# Modular_RFPA_v103_DFM_03_26_22.net
KiCad netlist of a schematic drawn in EAGLE
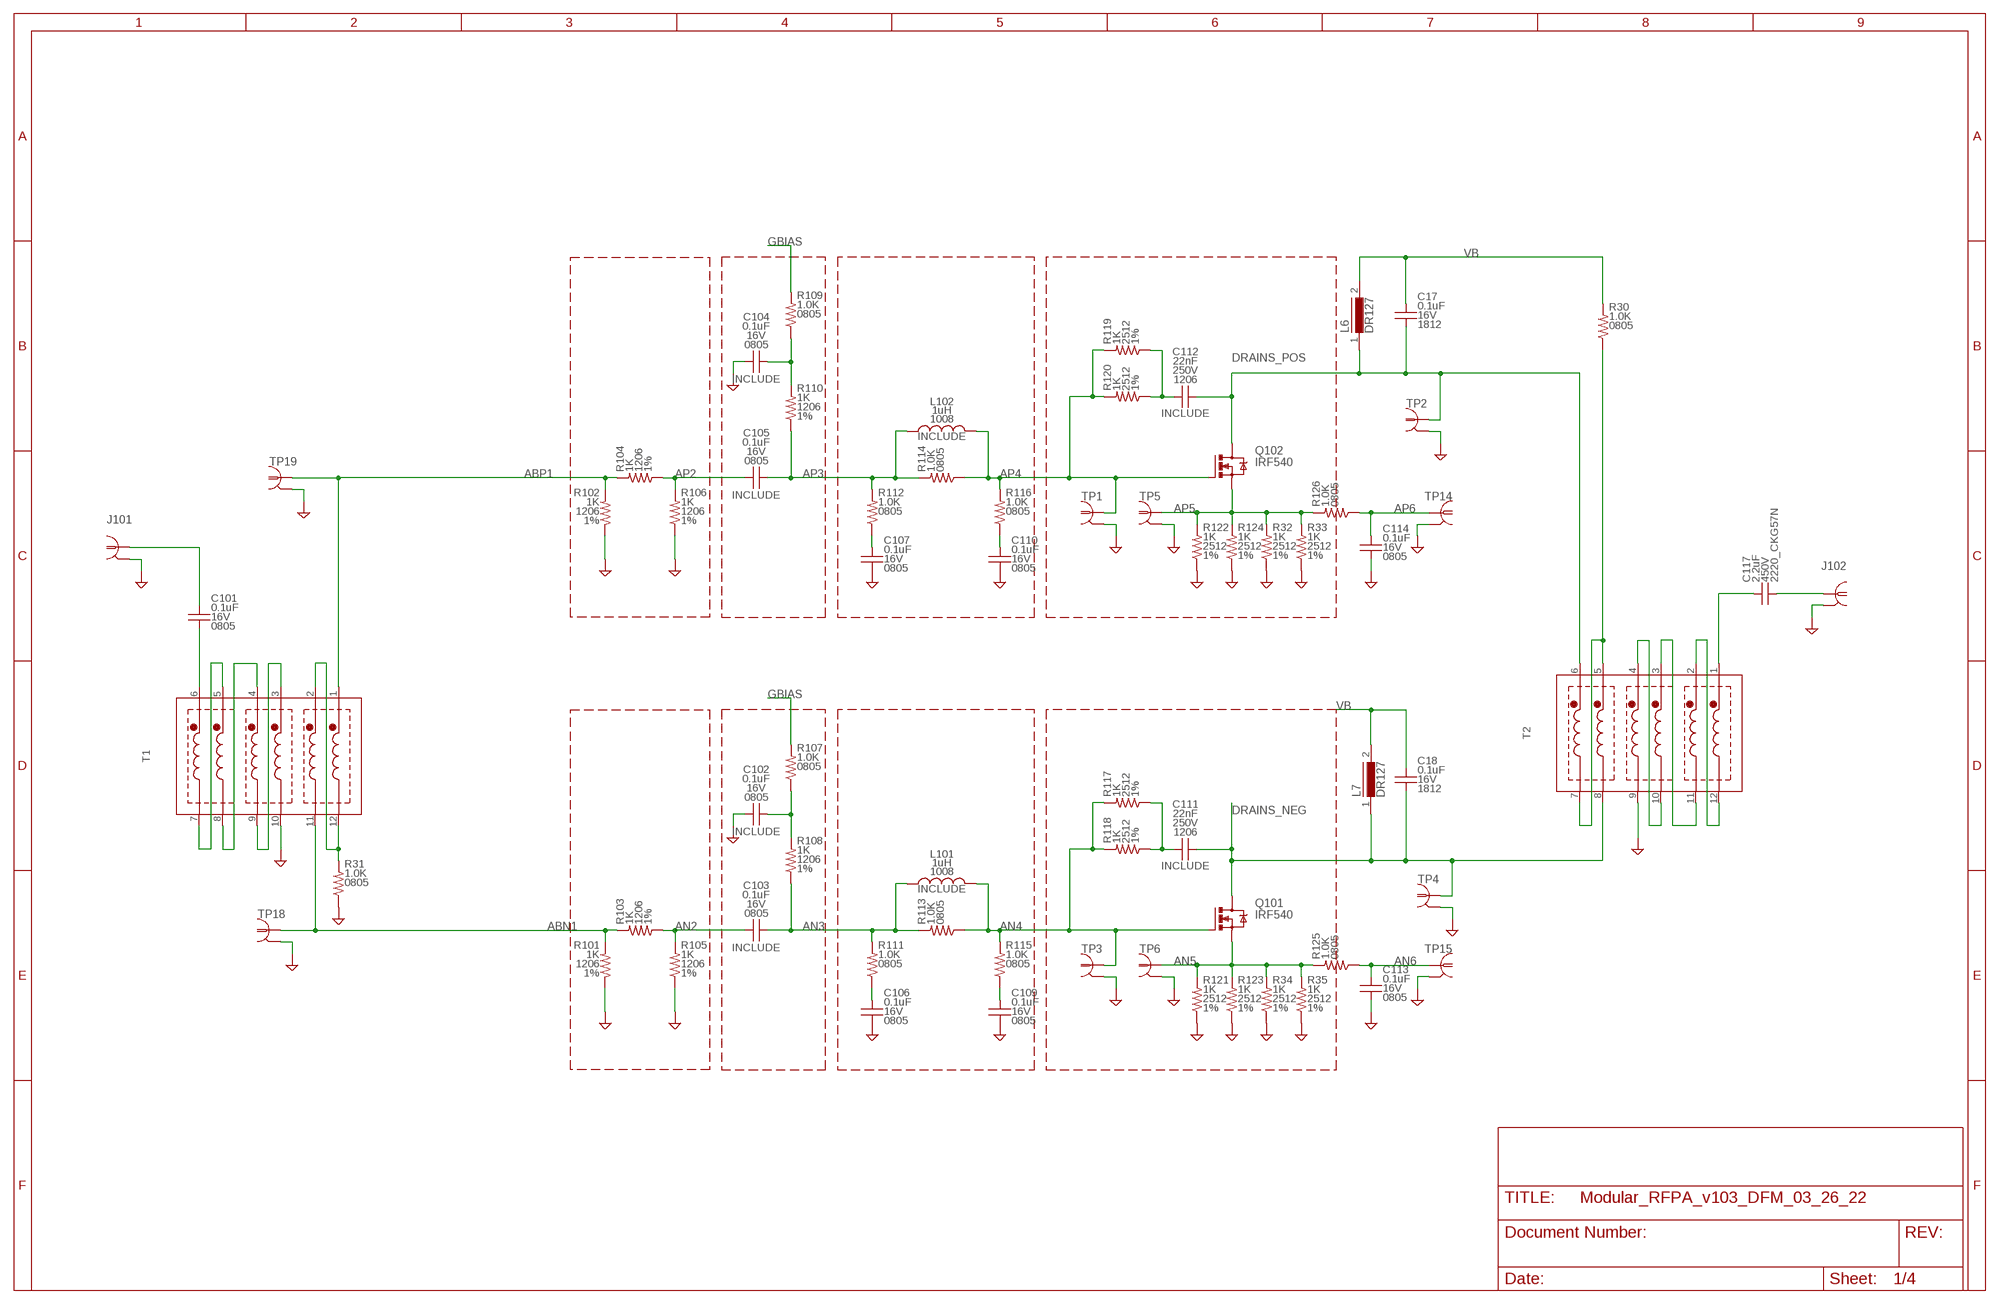
[diagram p0: schematic, sheet 1]
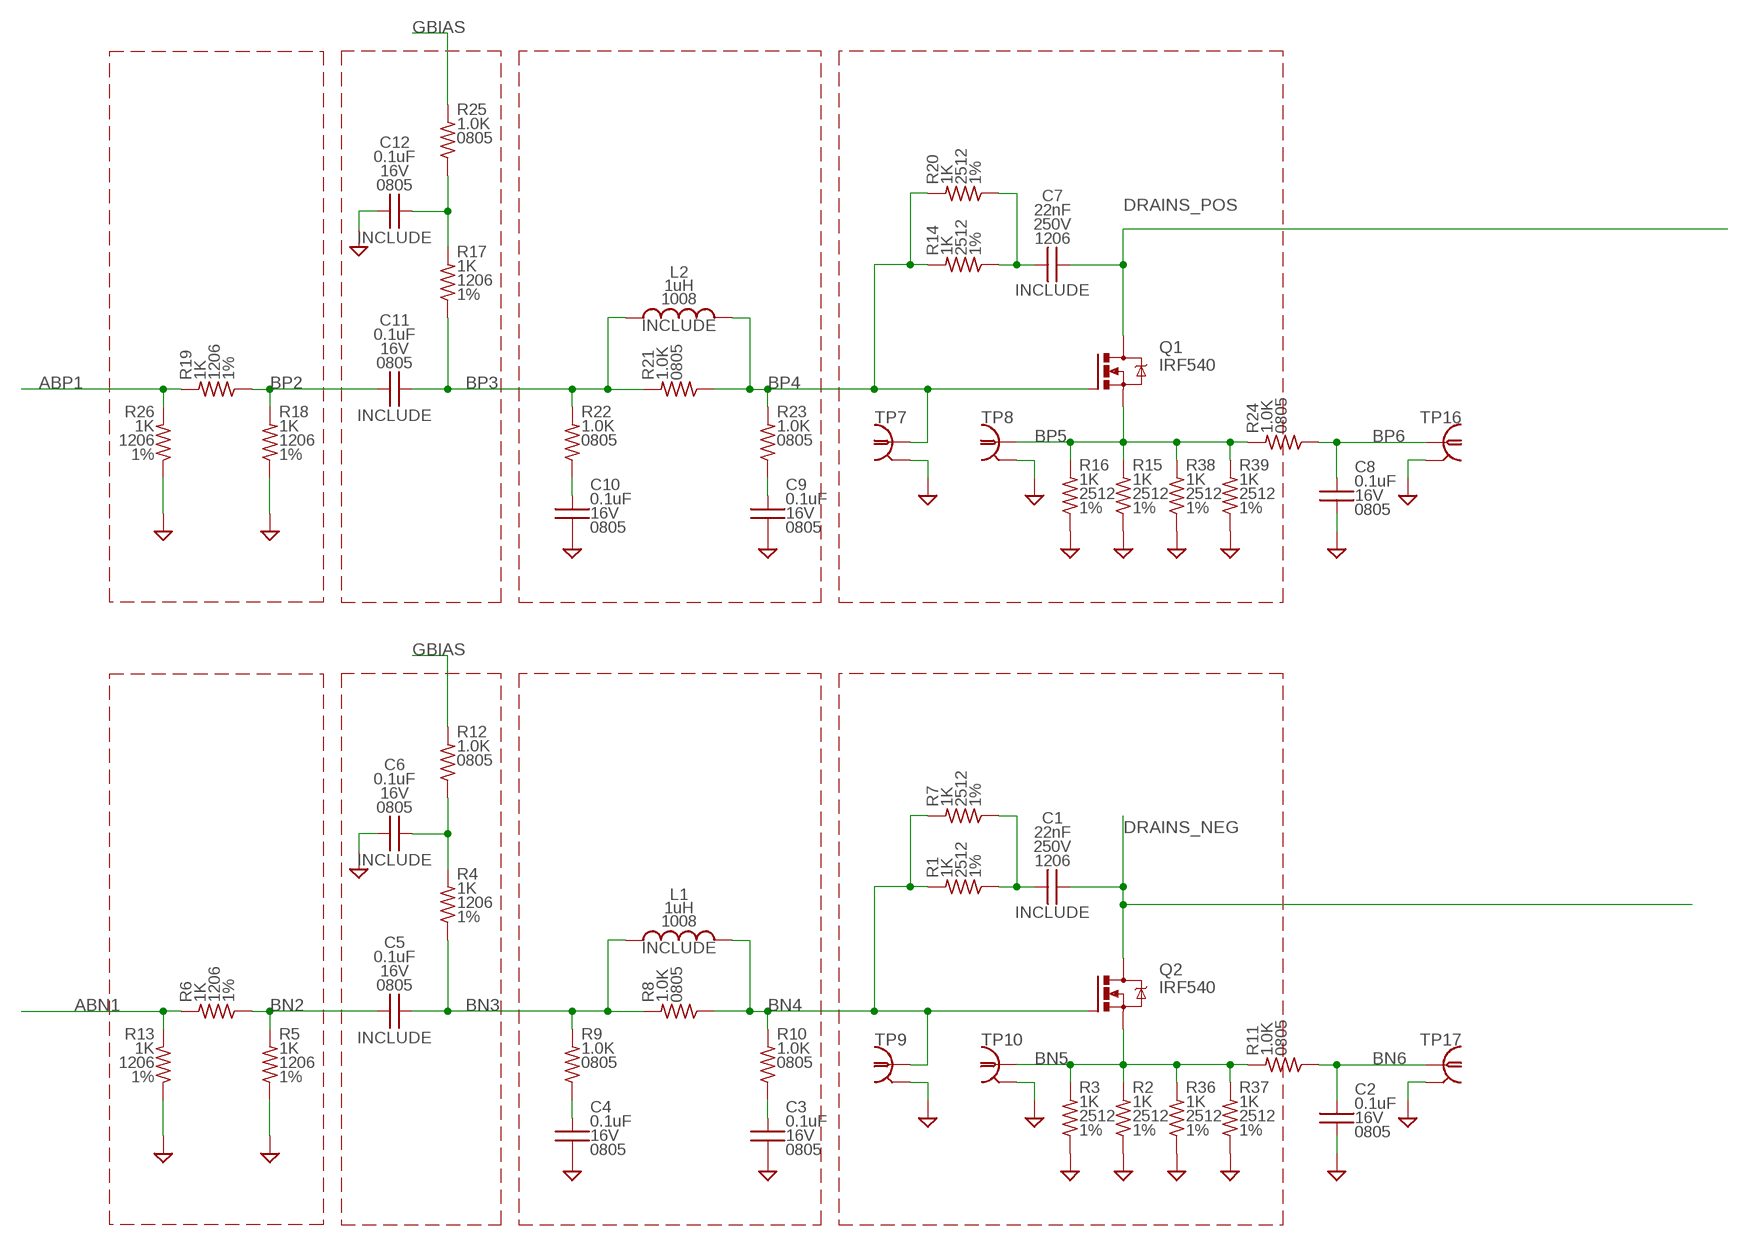
[diagram p1: schematic, sheet 2]
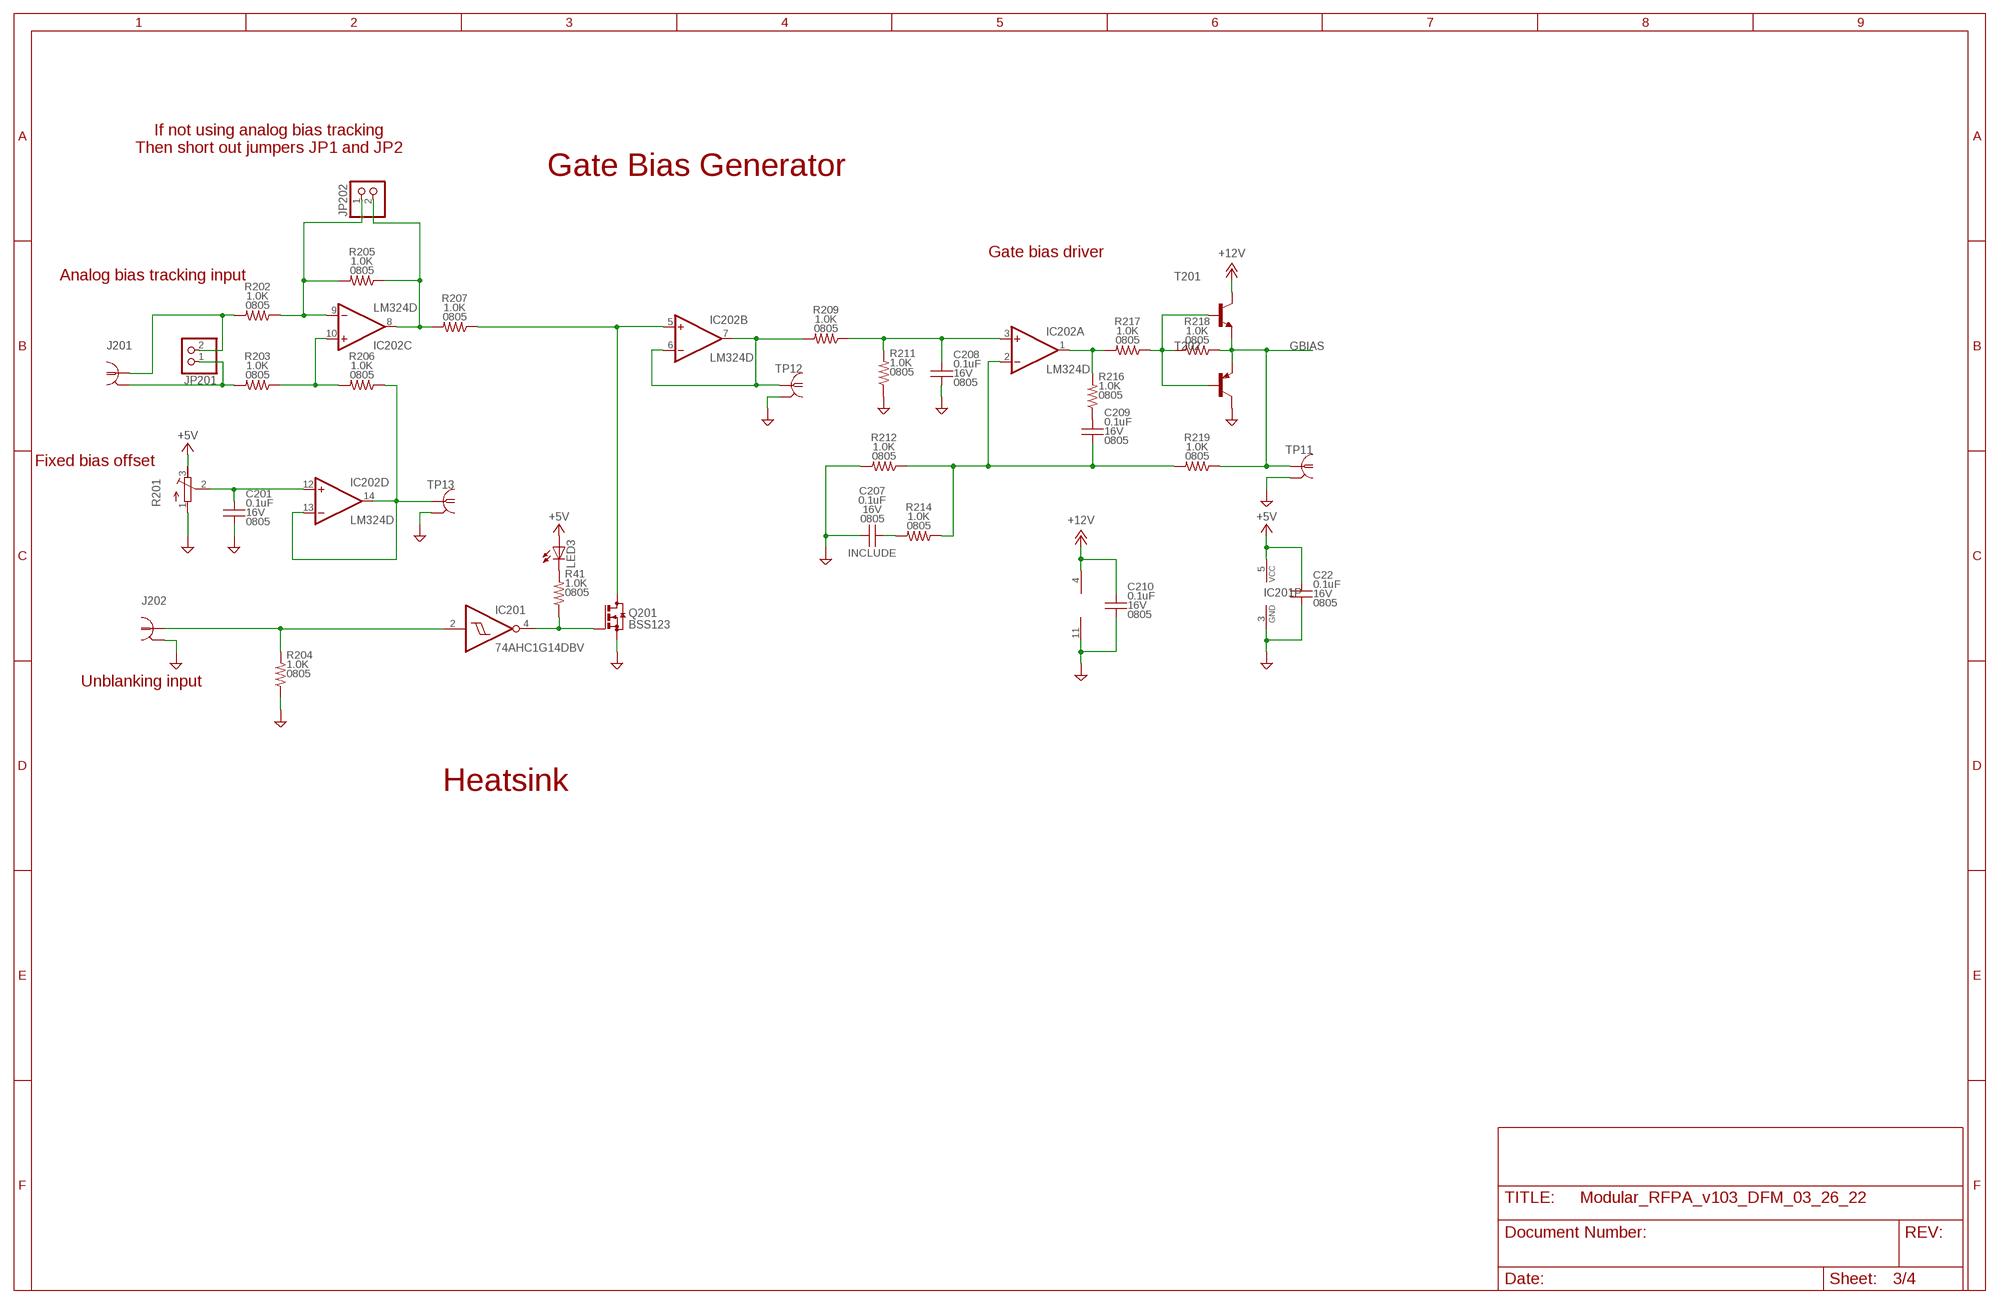
[diagram p2: schematic, sheet 3]
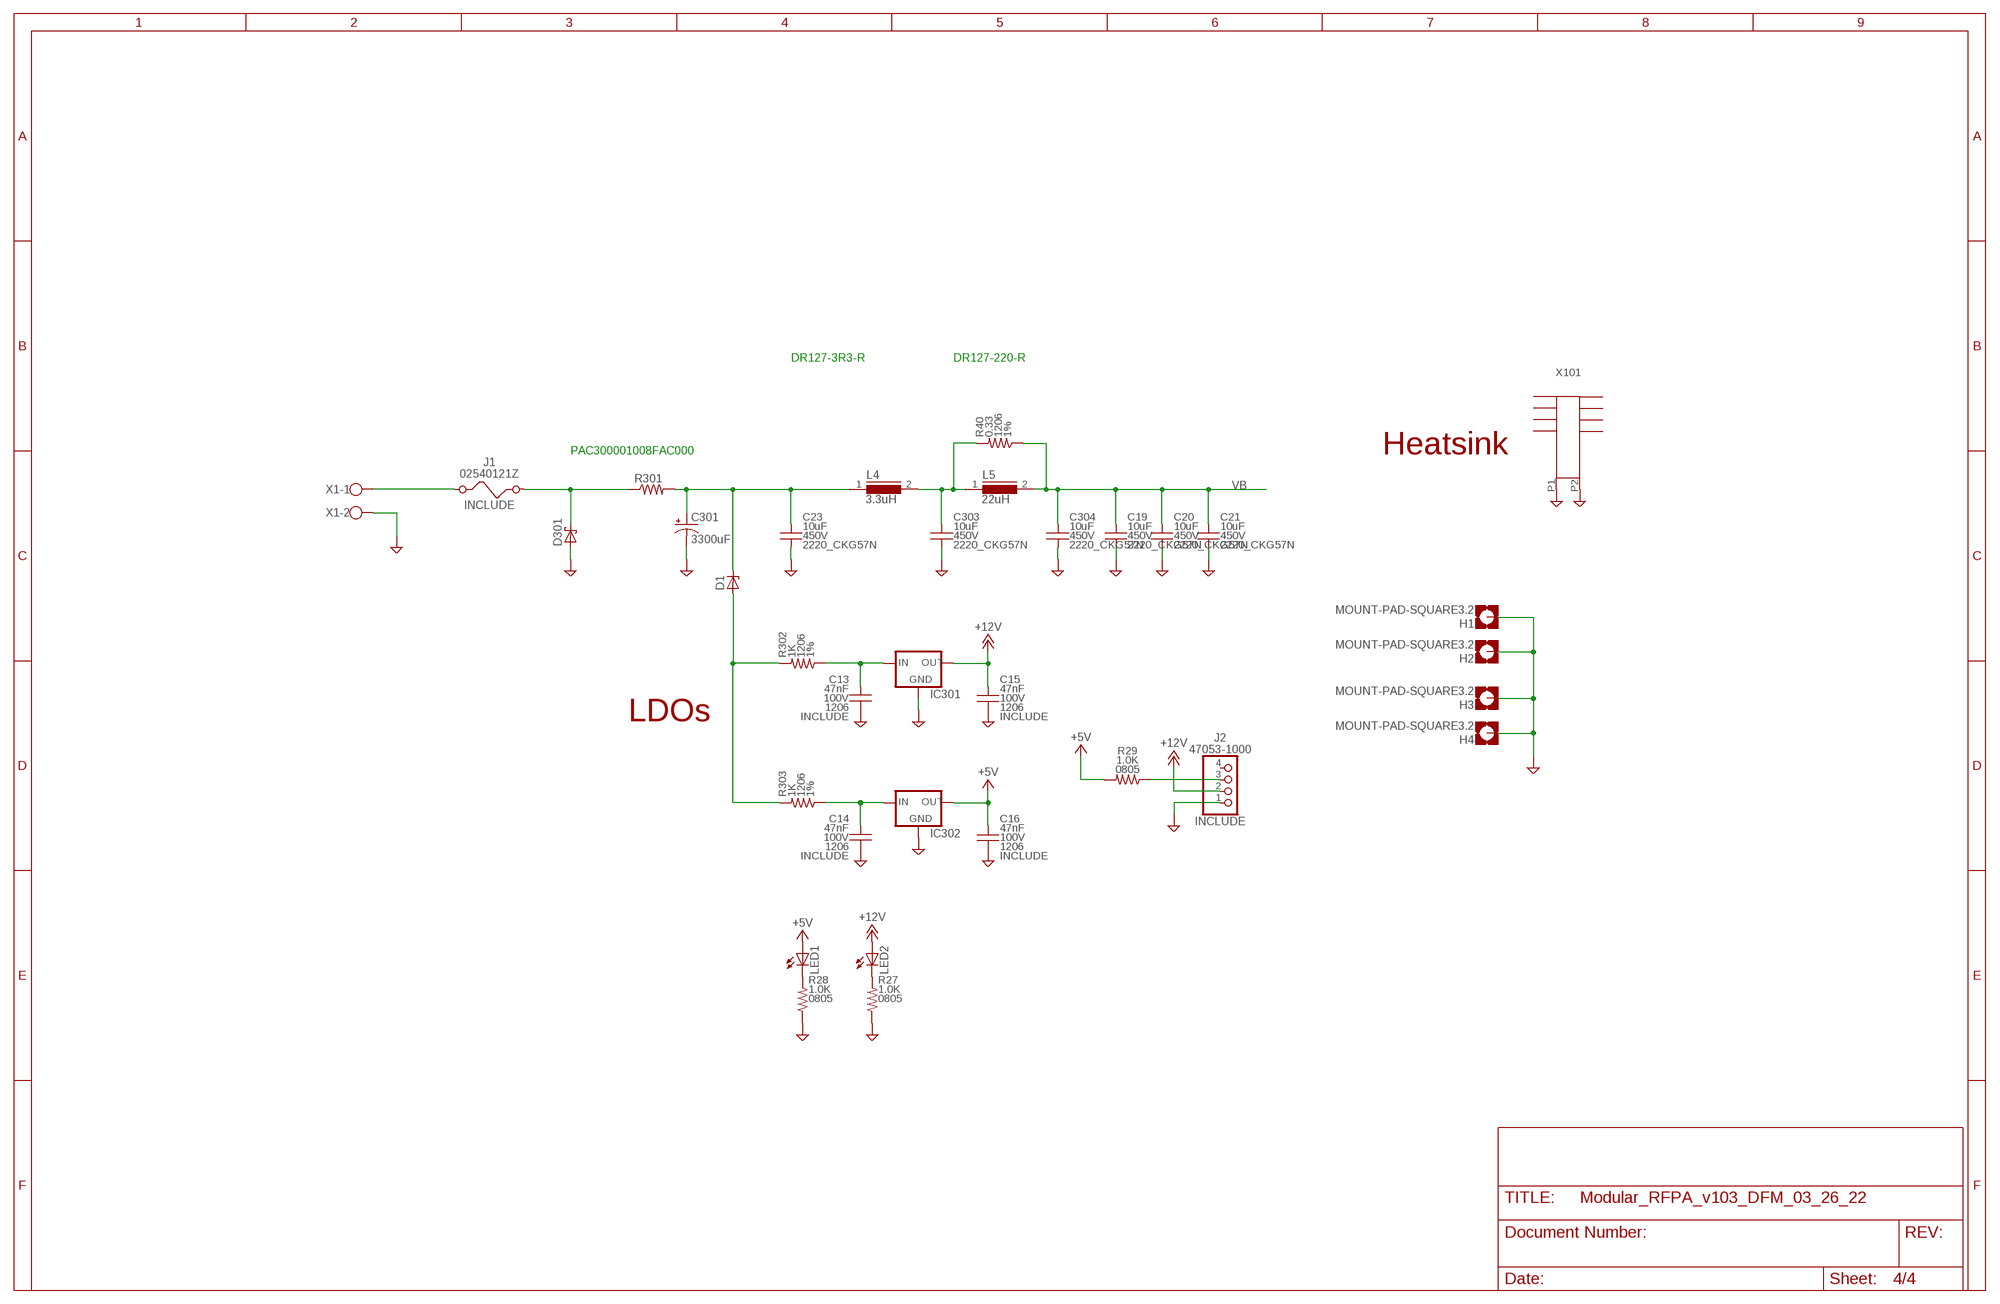
[diagram p3: schematic, sheet 4]

(export (version "E")
  (design (tool "Eeschema 10.0.6"))
  (components
    (comp (ref "C13")
      (value "47nF")
      (footprint "eagle-import:C1206")
      (fields (field (name "PARTNO") "C3216C0G2A473J115AC") (field (name "VOLTAGE") "100V"))
      (libsource (lib "eagle-import") (part "CC1206C-47N-100V-5%-1206-NP0"))
    )
    (comp (ref "C14")
      (value "47nF")
      (footprint "eagle-import:C1206")
      (fields (field (name "PARTNO") "C3216C0G2A473J115AC") (field (name "VOLTAGE") "100V"))
      (libsource (lib "eagle-import") (part "CC1206C-47N-100V-5%-1206-NP0"))
    )
    (comp (ref "C15")
      (value "47nF")
      (footprint "eagle-import:C1206")
      (fields (field (name "PARTNO") "C3216C0G2A473J115AC") (field (name "VOLTAGE") "100V"))
      (libsource (lib "eagle-import") (part "CC1206C-47N-100V-5%-1206-NP0"))
    )
    (comp (ref "C16")
      (value "47nF")
      (footprint "eagle-import:C1206")
      (fields (field (name "PARTNO") "C3216C0G2A473J115AC") (field (name "VOLTAGE") "100V"))
      (libsource (lib "eagle-import") (part "CC1206C-47N-100V-5%-1206-NP0"))
    )
    (comp (ref "C19")
      (value "10uF")
      (footprint "eagle-import:C2220_CKG57N")
      (fields (field (name "PARTNO") "CKG57NX7T2W225M500JJ") (field (name "VOLTAGE") "450V"))
      (libsource (lib "eagle-import") (part "CC2220_CKG57NC-2.2U-450V-20%-2220-X7T"))
    )
    (comp (ref "C20")
      (value "10uF")
      (footprint "eagle-import:C2220_CKG57N")
      (fields (field (name "PARTNO") "CKG57NX7T2W225M500JJ") (field (name "VOLTAGE") "450V"))
      (libsource (lib "eagle-import") (part "CC2220_CKG57NC-2.2U-450V-20%-2220-X7T"))
    )
    (comp (ref "C21")
      (value "10uF")
      (footprint "eagle-import:C2220_CKG57N")
      (fields (field (name "PARTNO") "CKG57NX7T2W225M500JJ") (field (name "VOLTAGE") "450V"))
      (libsource (lib "eagle-import") (part "CC2220_CKG57NC-2.2U-450V-20%-2220-X7T"))
    )
    (comp (ref "C23")
      (value "10uF")
      (footprint "eagle-import:C2220_CKG57N")
      (fields (field (name "PARTNO") "CKG57NX7T2W225M500JJ") (field (name "VOLTAGE") "450V"))
      (libsource (lib "eagle-import") (part "CC2220_CKG57NC-2.2U-450V-20%-2220-X7T"))
    )
    (comp (ref "C301")
      (value "3300uF")
      (footprint "eagle-import:EB25D")
      (libsource (lib "eagle-import") (part "CPOL-USE10-25"))
    )
    (comp (ref "C303")
      (value "10uF")
      (footprint "eagle-import:C2220_CKG57N")
      (fields (field (name "PARTNO") "CKG57NX7T2W225M500JJ") (field (name "VOLTAGE") "450V"))
      (libsource (lib "eagle-import") (part "CC2220_CKG57NC-2.2U-450V-20%-2220-X7T"))
    )
    (comp (ref "C304")
      (value "10uF")
      (footprint "eagle-import:C2220_CKG57N")
      (fields (field (name "PARTNO") "CKG57NX7T2W225M500JJ") (field (name "VOLTAGE") "450V"))
      (libsource (lib "eagle-import") (part "CC2220_CKG57NC-2.2U-450V-20%-2220-X7T"))
    )
    (comp (ref "D1")
      (value "ZENER-DIODEDO41Z10")
      (footprint "eagle-import:DO41Z10")
      (libsource (lib "eagle-import") (part "ZENER-DIODEDO41Z10"))
    )
    (comp (ref "D301")
      (value "SCHOTTKY-DIODESMC")
      (footprint "eagle-import:SMC")
      (libsource (lib "eagle-import") (part "SCHOTTKY-DIODESMC"))
    )
    (comp (ref "H1")
      (value "MOUNT-PAD-SQUARE3.2")
      (footprint "eagle-import:3,2-PAD-SQUARE")
      (libsource (lib "eagle-import") (part "MOUNT-PAD-SQUARE3.2"))
    )
    (comp (ref "H2")
      (value "MOUNT-PAD-SQUARE3.2")
      (footprint "eagle-import:3,2-PAD-SQUARE")
      (libsource (lib "eagle-import") (part "MOUNT-PAD-SQUARE3.2"))
    )
    (comp (ref "H3")
      (value "MOUNT-PAD-SQUARE3.2")
      (footprint "eagle-import:3,2-PAD-SQUARE")
      (libsource (lib "eagle-import") (part "MOUNT-PAD-SQUARE3.2"))
    )
    (comp (ref "H4")
      (value "MOUNT-PAD-SQUARE3.2")
      (footprint "eagle-import:3,2-PAD-SQUARE")
      (libsource (lib "eagle-import") (part "MOUNT-PAD-SQUARE3.2"))
    )
    (comp (ref "IC301")
      (value "78XXS")
      (footprint "eagle-import:78XXS")
      (libsource (lib "eagle-import") (part "78XXS"))
    )
    (comp (ref "IC302")
      (value "78XXS")
      (footprint "eagle-import:78XXS")
      (libsource (lib "eagle-import") (part "78XXS"))
    )
    (comp (ref "J1")
      (value "FUSE_2P")
      (footprint "eagle-import:02540121Z")
      (fields (field (name "PARTNO") "02540121Z"))
      (libsource (lib "eagle-import") (part "FUSE_2P"))
    )
    (comp (ref "J2")
      (value "KK_PCFAN")
      (footprint "eagle-import:47053-1000")
      (fields (field (name "PARTNO") "47053-1000"))
      (libsource (lib "eagle-import") (part "KK_PCFAN"))
    )
    (comp (ref "L4")
      (value "3.3uH")
      (footprint "eagle-import:DR127")
      (libsource (lib "eagle-import") (part "DR127"))
    )
    (comp (ref "L5")
      (value "22uH")
      (footprint "eagle-import:DR127")
      (libsource (lib "eagle-import") (part "DR127"))
    )
    (comp (ref "LED1")
      (value "LED5MM")
      (footprint "eagle-import:LED5MM")
      (libsource (lib "eagle-import") (part "LED5MM"))
    )
    (comp (ref "LED2")
      (value "LED5MM")
      (footprint "eagle-import:LED5MM")
      (libsource (lib "eagle-import") (part "LED5MM"))
    )
    (comp (ref "R27")
      (value "1.0K")
      (footprint "eagle-import:0805_IPC-7351B")
      (libsource (lib "eagle-import") (part "R0805_IPCR-1.0K-0.1%-0805-0.1W"))
    )
    (comp (ref "R28")
      (value "1.0K")
      (footprint "eagle-import:0805_IPC-7351B")
      (libsource (lib "eagle-import") (part "R0805_IPCR-1.0K-0.1%-0805-0.1W"))
    )
    (comp (ref "R29")
      (value "1.0K")
      (footprint "eagle-import:0805_IPC-7351B")
      (fields (field (name "PACKAGE") "0805"))
      (libsource (lib "eagle-import") (part "R0805_IPCR-1.0K-0.1%-0805-0.1W"))
    )
    (comp (ref "R40")
      (value "0.33")
      (footprint "eagle-import:R1206")
      (fields (field (name "POWER") "0.25"))
      (libsource (lib "eagle-import") (part "RR1206R-1.0K-1%-1206-0.25W"))
    )
    (comp (ref "R301")
      (value "R-US_0817/7V")
      (footprint "eagle-import:P0817V")
      (libsource (lib "eagle-import") (part "R-US_0817/7V"))
    )
    (comp (ref "R302")
      (value "1K")
      (footprint "eagle-import:R1206")
      (fields (field (name "POWER") "0.25"))
      (libsource (lib "eagle-import") (part "RR1206R-1.0K-1%-1206-0.25W"))
    )
    (comp (ref "R303")
      (value "1K")
      (footprint "eagle-import:R1206")
      (fields (field (name "POWER") "0.25"))
      (libsource (lib "eagle-import") (part "RR1206R-1.0K-1%-1206-0.25W"))
    )
    (comp (ref "X1")
      (value "W237-102")
      (footprint "eagle-import:W237-102")
      (fields (field (name "MPN") "237-102"))
      (libsource (lib "eagle-import") (part "W237-102"))
    )
    (comp (ref "X101")
      (value "HEATSINK_OMNI_DUAL30-75-D")
      (footprint "eagle-import:OMNI-UNI-30-75-D")
      (libsource (lib "eagle-import") (part "HEATSINK_OMNI_DUAL30-75-D"))
    )
    (comp (ref "C1")
      (value "22nF")
      (footprint "eagle-import:C1206")
      (fields
        (field (name "BOM") "INCLUDE")
        (field (name "PACKAGE") "1206")
        (field (name "PARTNO") "C3216NP02E223J160AA")
        (field (name "VOLTAGE") "250V")
      )
      (libsource (lib "eagle-import") (part "CC1206C-22N-250V-5%-1206-NP0"))
    )
    (comp (ref "C2")
      (value "0.1uF")
      (footprint "eagle-import:0805_IPC-7351B")
      (fields (field (name "VOLTAGE") "16V"))
      (libsource (lib "eagle-import") (part "C0805_IPCC-0.1U-16V-0805-X7R"))
    )
    (comp (ref "C3")
      (value "0.1uF")
      (footprint "eagle-import:0805_IPC-7351B")
      (fields (field (name "VOLTAGE") "16V"))
      (libsource (lib "eagle-import") (part "C0805_IPCC-0.1U-16V-0805-X7R"))
    )
    (comp (ref "C4")
      (value "0.1uF")
      (footprint "eagle-import:0805_IPC-7351B")
      (fields (field (name "VOLTAGE") "16V"))
      (libsource (lib "eagle-import") (part "C0805_IPCC-0.1U-16V-0805-X7R"))
    )
    (comp (ref "C5")
      (value "0.1uF")
      (footprint "eagle-import:0805_IPC-7351B")
      (fields (field (name "PACKAGE") "0805") (field (name "VOLTAGE") "16V") (field (name "BOM") "INCLUDE"))
      (libsource (lib "eagle-import") (part "C0805_IPCC-0.1U-16V-0805-X7R"))
    )
    (comp (ref "C6")
      (value "0.1uF")
      (footprint "eagle-import:0805_IPC-7351B")
      (fields (field (name "PACKAGE") "0805") (field (name "VOLTAGE") "16V") (field (name "BOM") "INCLUDE"))
      (libsource (lib "eagle-import") (part "C0805_IPCC-0.1U-16V-0805-X7R"))
    )
    (comp (ref "C7")
      (value "22nF")
      (footprint "eagle-import:C1206")
      (fields
        (field (name "BOM") "INCLUDE")
        (field (name "PACKAGE") "1206")
        (field (name "PARTNO") "C3216NP02E223J160AA")
        (field (name "VOLTAGE") "250V")
      )
      (libsource (lib "eagle-import") (part "CC1206C-22N-250V-5%-1206-NP0"))
    )
    (comp (ref "C8")
      (value "0.1uF")
      (footprint "eagle-import:0805_IPC-7351B")
      (fields (field (name "VOLTAGE") "16V"))
      (libsource (lib "eagle-import") (part "C0805_IPCC-0.1U-16V-0805-X7R"))
    )
    (comp (ref "C9")
      (value "0.1uF")
      (footprint "eagle-import:0805_IPC-7351B")
      (fields (field (name "VOLTAGE") "16V"))
      (libsource (lib "eagle-import") (part "C0805_IPCC-0.1U-16V-0805-X7R"))
    )
    (comp (ref "C10")
      (value "0.1uF")
      (footprint "eagle-import:0805_IPC-7351B")
      (fields (field (name "VOLTAGE") "16V"))
      (libsource (lib "eagle-import") (part "C0805_IPCC-0.1U-16V-0805-X7R"))
    )
    (comp (ref "C11")
      (value "0.1uF")
      (footprint "eagle-import:0805_IPC-7351B")
      (fields (field (name "PACKAGE") "0805") (field (name "VOLTAGE") "16V") (field (name "BOM") "INCLUDE"))
      (libsource (lib "eagle-import") (part "C0805_IPCC-0.1U-16V-0805-X7R"))
    )
    (comp (ref "C12")
      (value "0.1uF")
      (footprint "eagle-import:0805_IPC-7351B")
      (fields (field (name "PACKAGE") "0805") (field (name "VOLTAGE") "16V") (field (name "BOM") "INCLUDE"))
      (libsource (lib "eagle-import") (part "C0805_IPCC-0.1U-16V-0805-X7R"))
    )
    (comp (ref "L1")
      (value "1uH")
      (footprint "eagle-import:L1008")
      (fields (field (name "PARTNO") "1008CS-102XJEC"))
      (libsource (lib "eagle-import") (part "L_CHIP1008L-1.0U-AIR-5%-1008-0.37A"))
    )
    (comp (ref "L2")
      (value "1uH")
      (footprint "eagle-import:L1008")
      (fields (field (name "PARTNO") "1008CS-102XJEC"))
      (libsource (lib "eagle-import") (part "L_CHIP1008L-1.0U-AIR-5%-1008-0.37A"))
    )
    (comp (ref "Q1")
      (value "IRF540")
      (footprint "eagle-import:TO220BV")
      (libsource (lib "eagle-import") (part "IRF540"))
    )
    (comp (ref "Q2")
      (value "IRF540")
      (footprint "eagle-import:TO220BV")
      (libsource (lib "eagle-import") (part "IRF540"))
    )
    (comp (ref "R1")
      (value "1K")
      (footprint "eagle-import:R2512")
      (fields (field (name "POWER") "1"))
      (libsource (lib "eagle-import") (part "RR2512R-1K-1%-2512-1W"))
    )
    (comp (ref "R2")
      (value "1K")
      (footprint "eagle-import:R2512")
      (fields (field (name "POWER") "1"))
      (libsource (lib "eagle-import") (part "RR2512R-1K-1%-2512-1W"))
    )
    (comp (ref "R3")
      (value "1K")
      (footprint "eagle-import:R2512")
      (fields (field (name "POWER") "1"))
      (libsource (lib "eagle-import") (part "RR2512R-1K-1%-2512-1W"))
    )
    (comp (ref "R4")
      (value "1K")
      (footprint "eagle-import:R1206")
      (fields (field (name "POWER") "0.25"))
      (libsource (lib "eagle-import") (part "RR1206R-1.0K-1%-1206-0.25W"))
    )
    (comp (ref "R5")
      (value "1K")
      (footprint "eagle-import:R1206")
      (fields (field (name "POWER") "0.25"))
      (libsource (lib "eagle-import") (part "RR1206R-1.0K-1%-1206-0.25W"))
    )
    (comp (ref "R6")
      (value "1K")
      (footprint "eagle-import:R1206")
      (fields (field (name "POWER") "0.25"))
      (libsource (lib "eagle-import") (part "RR1206R-1.0K-1%-1206-0.25W"))
    )
    (comp (ref "R7")
      (value "1K")
      (footprint "eagle-import:R2512")
      (fields (field (name "POWER") "1"))
      (libsource (lib "eagle-import") (part "RR2512R-1K-1%-2512-1W"))
    )
    (comp (ref "R8")
      (value "1.0K")
      (footprint "eagle-import:0805_IPC-7351B")
      (libsource (lib "eagle-import") (part "R0805_IPCR-1.0K-0.1%-0805-0.1W"))
    )
    (comp (ref "R9")
      (value "1.0K")
      (footprint "eagle-import:0805_IPC-7351B")
      (libsource (lib "eagle-import") (part "R0805_IPCR-1.0K-0.1%-0805-0.1W"))
    )
    (comp (ref "R10")
      (value "1.0K")
      (footprint "eagle-import:0805_IPC-7351B")
      (libsource (lib "eagle-import") (part "R0805_IPCR-1.0K-0.1%-0805-0.1W"))
    )
    (comp (ref "R11")
      (value "1.0K")
      (footprint "eagle-import:0805_IPC-7351B")
      (libsource (lib "eagle-import") (part "R0805_IPCR-1.0K-0.1%-0805-0.1W"))
    )
    (comp (ref "R12")
      (value "1.0K")
      (footprint "eagle-import:0805_IPC-7351B")
      (libsource (lib "eagle-import") (part "R0805_IPCR-1.0K-0.1%-0805-0.1W"))
    )
    (comp (ref "R13")
      (value "1K")
      (footprint "eagle-import:R1206")
      (fields (field (name "POWER") "0.25"))
      (libsource (lib "eagle-import") (part "RR1206R-1.0K-1%-1206-0.25W"))
    )
    (comp (ref "R14")
      (value "1K")
      (footprint "eagle-import:R2512")
      (fields (field (name "POWER") "1"))
      (libsource (lib "eagle-import") (part "RR2512R-1K-1%-2512-1W"))
    )
    (comp (ref "R15")
      (value "1K")
      (footprint "eagle-import:R2512")
      (fields (field (name "POWER") "1"))
      (libsource (lib "eagle-import") (part "RR2512R-1K-1%-2512-1W"))
    )
    (comp (ref "R16")
      (value "1K")
      (footprint "eagle-import:R2512")
      (fields (field (name "POWER") "1"))
      (libsource (lib "eagle-import") (part "RR2512R-1K-1%-2512-1W"))
    )
    (comp (ref "R17")
      (value "1K")
      (footprint "eagle-import:R1206")
      (fields (field (name "POWER") "0.25"))
      (libsource (lib "eagle-import") (part "RR1206R-1.0K-1%-1206-0.25W"))
    )
    (comp (ref "R18")
      (value "1K")
      (footprint "eagle-import:R1206")
      (fields (field (name "POWER") "0.25"))
      (libsource (lib "eagle-import") (part "RR1206R-1.0K-1%-1206-0.25W"))
    )
    (comp (ref "R19")
      (value "1K")
      (footprint "eagle-import:R1206")
      (fields (field (name "POWER") "0.25"))
      (libsource (lib "eagle-import") (part "RR1206R-1.0K-1%-1206-0.25W"))
    )
    (comp (ref "R20")
      (value "1K")
      (footprint "eagle-import:R2512")
      (fields (field (name "POWER") "1"))
      (libsource (lib "eagle-import") (part "RR2512R-1K-1%-2512-1W"))
    )
    (comp (ref "R21")
      (value "1.0K")
      (footprint "eagle-import:0805_IPC-7351B")
      (libsource (lib "eagle-import") (part "R0805_IPCR-1.0K-0.1%-0805-0.1W"))
    )
    (comp (ref "R22")
      (value "1.0K")
      (footprint "eagle-import:0805_IPC-7351B")
      (libsource (lib "eagle-import") (part "R0805_IPCR-1.0K-0.1%-0805-0.1W"))
    )
    (comp (ref "R23")
      (value "1.0K")
      (footprint "eagle-import:0805_IPC-7351B")
      (libsource (lib "eagle-import") (part "R0805_IPCR-1.0K-0.1%-0805-0.1W"))
    )
    (comp (ref "R24")
      (value "1.0K")
      (footprint "eagle-import:0805_IPC-7351B")
      (libsource (lib "eagle-import") (part "R0805_IPCR-1.0K-0.1%-0805-0.1W"))
    )
    (comp (ref "R25")
      (value "1.0K")
      (footprint "eagle-import:0805_IPC-7351B")
      (libsource (lib "eagle-import") (part "R0805_IPCR-1.0K-0.1%-0805-0.1W"))
    )
    (comp (ref "R26")
      (value "1K")
      (footprint "eagle-import:R1206")
      (fields (field (name "POWER") "0.25"))
      (libsource (lib "eagle-import") (part "RR1206R-1.0K-1%-1206-0.25W"))
    )
    (comp (ref "R36")
      (value "1K")
      (footprint "eagle-import:R2512")
      (fields (field (name "POWER") "1"))
      (libsource (lib "eagle-import") (part "RR2512R-1K-1%-2512-1W"))
    )
    (comp (ref "R37")
      (value "1K")
      (footprint "eagle-import:R2512")
      (fields (field (name "POWER") "1"))
      (libsource (lib "eagle-import") (part "RR2512R-1K-1%-2512-1W"))
    )
    (comp (ref "R38")
      (value "1K")
      (footprint "eagle-import:R2512")
      (fields (field (name "POWER") "1"))
      (libsource (lib "eagle-import") (part "RR2512R-1K-1%-2512-1W"))
    )
    (comp (ref "R39")
      (value "1K")
      (footprint "eagle-import:R2512")
      (fields (field (name "POWER") "1"))
      (libsource (lib "eagle-import") (part "RR2512R-1K-1%-2512-1W"))
    )
    (comp (ref "TP7")
      (value "PROBE_TPTP_5MM")
      (footprint "eagle-import:PROBE_TP_5MM")
      (libsource (lib "eagle-import") (part "PROBE_TPTP_5MM"))
    )
    (comp (ref "TP8")
      (value "PROBE_TPTP_7P5MM")
      (footprint "eagle-import:PROBE_TP_7P5MM")
      (libsource (lib "eagle-import") (part "PROBE_TPTP_7P5MM"))
    )
    (comp (ref "TP9")
      (value "PROBE_TPTP_5MM")
      (footprint "eagle-import:PROBE_TP_5MM")
      (libsource (lib "eagle-import") (part "PROBE_TPTP_5MM"))
    )
    (comp (ref "TP10")
      (value "PROBE_TPTP_5MM")
      (footprint "eagle-import:PROBE_TP_5MM")
      (libsource (lib "eagle-import") (part "PROBE_TPTP_5MM"))
    )
    (comp (ref "TP16")
      (value "PROBE_TPTP_5MM")
      (footprint "eagle-import:PROBE_TP_5MM")
      (libsource (lib "eagle-import") (part "PROBE_TPTP_5MM"))
    )
    (comp (ref "TP17")
      (value "PROBE_TPTP_7P5MM")
      (footprint "eagle-import:PROBE_TP_7P5MM")
      (libsource (lib "eagle-import") (part "PROBE_TPTP_7P5MM"))
    )
    (comp (ref "C22")
      (value "0.1uF")
      (footprint "eagle-import:0805_IPC-7351B")
      (fields (field (name "VOLTAGE") "16V"))
      (libsource (lib "eagle-import") (part "C0805_IPCC-0.1U-16V-0805-X7R"))
    )
    (comp (ref "C201")
      (value "0.1uF")
      (footprint "eagle-import:0805_IPC-7351B")
      (fields (field (name "VOLTAGE") "16V"))
      (libsource (lib "eagle-import") (part "C0805_IPCC-0.1U-16V-0805-X7R"))
    )
    (comp (ref "C207")
      (value "0.1uF")
      (footprint "eagle-import:0805_IPC-7351B")
      (fields (field (name "PACKAGE") "0805") (field (name "VOLTAGE") "16V") (field (name "BOM") "INCLUDE"))
      (libsource (lib "eagle-import") (part "C0805_IPCC-0.1U-16V-0805-X7R"))
    )
    (comp (ref "C208")
      (value "0.1uF")
      (footprint "eagle-import:0805_IPC-7351B")
      (fields (field (name "VOLTAGE") "16V"))
      (libsource (lib "eagle-import") (part "C0805_IPCC-0.1U-16V-0805-X7R"))
    )
    (comp (ref "C209")
      (value "0.1uF")
      (footprint "eagle-import:0805_IPC-7351B")
      (fields (field (name "VOLTAGE") "16V"))
      (libsource (lib "eagle-import") (part "C0805_IPCC-0.1U-16V-0805-X7R"))
    )
    (comp (ref "C210")
      (value "0.1uF")
      (footprint "eagle-import:0805_IPC-7351B")
      (fields (field (name "VOLTAGE") "16V"))
      (libsource (lib "eagle-import") (part "C0805_IPCC-0.1U-16V-0805-X7R"))
    )
    (comp (ref "IC201")
      (value "74AHC1G14DBV")
      (footprint "eagle-import:SOT23-5")
      (libsource (lib "eagle-import") (part "741G14DBVAHC"))
    )
    (comp (ref "IC202")
      (value "LM324D")
      (footprint "eagle-import:SO14")
      (libsource (lib "eagle-import") (part "LM324D"))
    )
    (comp (ref "J201")
      (value "COAXBNC_EDGE")
      (footprint "eagle-import:BNC_EDGE")
      (libsource (lib "eagle-import") (part "COAXBNC_EDGE"))
    )
    (comp (ref "J202")
      (value "COAXBNC_EDGE")
      (footprint "eagle-import:BNC_EDGE")
      (libsource (lib "eagle-import") (part "COAXBNC_EDGE"))
    )
    (comp (ref "JP201")
      (value "PINHD-1X2")
      (footprint "eagle-import:1X02")
      (libsource (lib "eagle-import") (part "PINHD-1X2"))
    )
    (comp (ref "JP202")
      (value "PINHD-1X2")
      (footprint "eagle-import:1X02")
      (libsource (lib "eagle-import") (part "PINHD-1X2"))
    )
    (comp (ref "LED3")
      (value "LED5MM")
      (footprint "eagle-import:LED5MM")
      (libsource (lib "eagle-import") (part "LED5MM"))
    )
    (comp (ref "Q201")
      (value "BSS123")
      (footprint "eagle-import:SOT23")
      (libsource (lib "eagle-import") (part "BSS123"))
    )
    (comp (ref "R41")
      (value "1.0K")
      (footprint "eagle-import:0805_IPC-7351B")
      (libsource (lib "eagle-import") (part "R0805_IPCR-1.0K-0.1%-0805-0.1W"))
    )
    (comp (ref "R201")
      (value "R-TRIMM3299W")
      (footprint "eagle-import:RTRIM3299W")
      (libsource (lib "eagle-import") (part "R-TRIMM3299W"))
    )
    (comp (ref "R202")
      (value "1.0K")
      (footprint "eagle-import:0805_IPC-7351B")
      (fields (field (name "PACKAGE") "0805"))
      (libsource (lib "eagle-import") (part "R0805_IPCR-1.0K-0.1%-0805-0.1W"))
    )
    (comp (ref "R203")
      (value "1.0K")
      (footprint "eagle-import:0805_IPC-7351B")
      (fields (field (name "PACKAGE") "0805"))
      (libsource (lib "eagle-import") (part "R0805_IPCR-1.0K-0.1%-0805-0.1W"))
    )
    (comp (ref "R204")
      (value "1.0K")
      (footprint "eagle-import:0805_IPC-7351B")
      (libsource (lib "eagle-import") (part "R0805_IPCR-1.0K-0.1%-0805-0.1W"))
    )
    (comp (ref "R205")
      (value "1.0K")
      (footprint "eagle-import:0805_IPC-7351B")
      (fields (field (name "PACKAGE") "0805"))
      (libsource (lib "eagle-import") (part "R0805_IPCR-1.0K-0.1%-0805-0.1W"))
    )
    (comp (ref "R206")
      (value "1.0K")
      (footprint "eagle-import:0805_IPC-7351B")
      (fields (field (name "PACKAGE") "0805"))
      (libsource (lib "eagle-import") (part "R0805_IPCR-1.0K-0.1%-0805-0.1W"))
    )
    (comp (ref "R207")
      (value "1.0K")
      (footprint "eagle-import:0805_IPC-7351B")
      (fields (field (name "PACKAGE") "0805"))
      (libsource (lib "eagle-import") (part "R0805_IPCR-1.0K-0.1%-0805-0.1W"))
    )
    (comp (ref "R209")
      (value "1.0K")
      (footprint "eagle-import:0805_IPC-7351B")
      (fields (field (name "PACKAGE") "0805"))
      (libsource (lib "eagle-import") (part "R0805_IPCR-1.0K-0.1%-0805-0.1W"))
    )
    (comp (ref "R211")
      (value "1.0K")
      (footprint "eagle-import:0805_IPC-7351B")
      (libsource (lib "eagle-import") (part "R0805_IPCR-1.0K-0.1%-0805-0.1W"))
    )
    (comp (ref "R212")
      (value "1.0K")
      (footprint "eagle-import:0805_IPC-7351B")
      (fields (field (name "PACKAGE") "0805"))
      (libsource (lib "eagle-import") (part "R0805_IPCR-1.0K-0.1%-0805-0.1W"))
    )
    (comp (ref "R214")
      (value "1.0K")
      (footprint "eagle-import:0805_IPC-7351B")
      (fields (field (name "PACKAGE") "0805"))
      (libsource (lib "eagle-import") (part "R0805_IPCR-1.0K-0.1%-0805-0.1W"))
    )
    (comp (ref "R216")
      (value "1.0K")
      (footprint "eagle-import:0805_IPC-7351B")
      (libsource (lib "eagle-import") (part "R0805_IPCR-1.0K-0.1%-0805-0.1W"))
    )
    (comp (ref "R217")
      (value "1.0K")
      (footprint "eagle-import:0805_IPC-7351B")
      (fields (field (name "PACKAGE") "0805"))
      (libsource (lib "eagle-import") (part "R0805_IPCR-1.0K-0.1%-0805-0.1W"))
    )
    (comp (ref "R218")
      (value "1.0K")
      (footprint "eagle-import:0805_IPC-7351B")
      (fields (field (name "PACKAGE") "0805"))
      (libsource (lib "eagle-import") (part "R0805_IPCR-1.0K-0.1%-0805-0.1W"))
    )
    (comp (ref "R219")
      (value "1.0K")
      (footprint "eagle-import:0805_IPC-7351B")
      (fields (field (name "PACKAGE") "0805"))
      (libsource (lib "eagle-import") (part "R0805_IPCR-1.0K-0.1%-0805-0.1W"))
    )
    (comp (ref "T201")
      (value "BC808-NPN-SOT23-BEC")
      (footprint "eagle-import:SOT23-BEC")
      (libsource (lib "eagle-import") (part "-NPN-SOT23-BECBC808"))
    )
    (comp (ref "T202")
      (value "BC807-16-PNP-SOT23-BEC")
      (footprint "eagle-import:SOT23-BEC")
      (libsource (lib "eagle-import") (part "-PNP-SOT23-BECBC807-16"))
    )
    (comp (ref "TP11")
      (value "PROBE_TPTP_5MM")
      (footprint "eagle-import:PROBE_TP_5MM")
      (libsource (lib "eagle-import") (part "PROBE_TPTP_5MM"))
    )
    (comp (ref "TP12")
      (value "PROBE_TPTP_5MM")
      (footprint "eagle-import:PROBE_TP_5MM")
      (libsource (lib "eagle-import") (part "PROBE_TPTP_5MM"))
    )
    (comp (ref "TP13")
      (value "PROBE_TPTP_5MM")
      (footprint "eagle-import:PROBE_TP_5MM")
      (libsource (lib "eagle-import") (part "PROBE_TPTP_5MM"))
    )
    (comp (ref "C17")
      (value "0.1uF")
      (footprint "eagle-import:C1812")
      (fields (field (name "VOLTAGE") "16V"))
      (libsource (lib "eagle-import") (part "CC1812"))
    )
    (comp (ref "C18")
      (value "0.1uF")
      (footprint "eagle-import:C1812")
      (fields (field (name "VOLTAGE") "16V"))
      (libsource (lib "eagle-import") (part "CC1812"))
    )
    (comp (ref "C101")
      (value "0.1uF")
      (footprint "eagle-import:0805_IPC-7351B")
      (fields (field (name "VOLTAGE") "16V"))
      (libsource (lib "eagle-import") (part "C0805_IPCC-0.1U-16V-0805-X7R"))
    )
    (comp (ref "C102")
      (value "0.1uF")
      (footprint "eagle-import:0805_IPC-7351B")
      (fields (field (name "PACKAGE") "0805") (field (name "VOLTAGE") "16V") (field (name "BOM") "INCLUDE"))
      (libsource (lib "eagle-import") (part "C0805_IPCC-0.1U-16V-0805-X7R"))
    )
    (comp (ref "C103")
      (value "0.1uF")
      (footprint "eagle-import:0805_IPC-7351B")
      (fields (field (name "PACKAGE") "0805") (field (name "VOLTAGE") "16V") (field (name "BOM") "INCLUDE"))
      (libsource (lib "eagle-import") (part "C0805_IPCC-0.1U-16V-0805-X7R"))
    )
    (comp (ref "C104")
      (value "0.1uF")
      (footprint "eagle-import:0805_IPC-7351B")
      (fields (field (name "PACKAGE") "0805") (field (name "VOLTAGE") "16V") (field (name "BOM") "INCLUDE"))
      (libsource (lib "eagle-import") (part "C0805_IPCC-0.1U-16V-0805-X7R"))
    )
    (comp (ref "C105")
      (value "0.1uF")
      (footprint "eagle-import:0805_IPC-7351B")
      (fields (field (name "PACKAGE") "0805") (field (name "VOLTAGE") "16V") (field (name "BOM") "INCLUDE"))
      (libsource (lib "eagle-import") (part "C0805_IPCC-0.1U-16V-0805-X7R"))
    )
    (comp (ref "C106")
      (value "0.1uF")
      (footprint "eagle-import:0805_IPC-7351B")
      (fields (field (name "VOLTAGE") "16V"))
      (libsource (lib "eagle-import") (part "C0805_IPCC-0.1U-16V-0805-X7R"))
    )
    (comp (ref "C107")
      (value "0.1uF")
      (footprint "eagle-import:0805_IPC-7351B")
      (fields (field (name "VOLTAGE") "16V"))
      (libsource (lib "eagle-import") (part "C0805_IPCC-0.1U-16V-0805-X7R"))
    )
    (comp (ref "C109")
      (value "0.1uF")
      (footprint "eagle-import:0805_IPC-7351B")
      (fields (field (name "VOLTAGE") "16V"))
      (libsource (lib "eagle-import") (part "C0805_IPCC-0.1U-16V-0805-X7R"))
    )
    (comp (ref "C110")
      (value "0.1uF")
      (footprint "eagle-import:0805_IPC-7351B")
      (fields (field (name "VOLTAGE") "16V"))
      (libsource (lib "eagle-import") (part "C0805_IPCC-0.1U-16V-0805-X7R"))
    )
    (comp (ref "C111")
      (value "22nF")
      (footprint "eagle-import:C1206")
      (fields
        (field (name "BOM") "INCLUDE")
        (field (name "PACKAGE") "1206")
        (field (name "PARTNO") "C3216NP02E223J160AA")
        (field (name "VOLTAGE") "250V")
      )
      (libsource (lib "eagle-import") (part "CC1206C-22N-250V-5%-1206-NP0"))
    )
    (comp (ref "C112")
      (value "22nF")
      (footprint "eagle-import:C1206")
      (fields
        (field (name "BOM") "INCLUDE")
        (field (name "PACKAGE") "1206")
        (field (name "PARTNO") "C3216NP02E223J160AA")
        (field (name "VOLTAGE") "250V")
      )
      (libsource (lib "eagle-import") (part "CC1206C-22N-250V-5%-1206-NP0"))
    )
    (comp (ref "C113")
      (value "0.1uF")
      (footprint "eagle-import:0805_IPC-7351B")
      (fields (field (name "VOLTAGE") "16V"))
      (libsource (lib "eagle-import") (part "C0805_IPCC-0.1U-16V-0805-X7R"))
    )
    (comp (ref "C114")
      (value "0.1uF")
      (footprint "eagle-import:0805_IPC-7351B")
      (fields (field (name "VOLTAGE") "16V"))
      (libsource (lib "eagle-import") (part "C0805_IPCC-0.1U-16V-0805-X7R"))
    )
    (comp (ref "C117")
      (value "2.2uF")
      (footprint "eagle-import:C2220_CKG57N")
      (fields (field (name "PARTNO") "CKG57NX7T2W225M500JJ") (field (name "VOLTAGE") "450V"))
      (libsource (lib "eagle-import") (part "CC2220_CKG57NC-2.2U-450V-20%-2220-X7T"))
    )
    (comp (ref "J101")
      (value "COAXBNC_EDGE")
      (footprint "eagle-import:BNC_EDGE")
      (libsource (lib "eagle-import") (part "COAXBNC_EDGE"))
    )
    (comp (ref "J102")
      (value "COAXBNC_EDGE")
      (footprint "eagle-import:BNC_EDGE")
      (libsource (lib "eagle-import") (part "COAXBNC_EDGE"))
    )
    (comp (ref "L6")
      (value "DR127")
      (footprint "eagle-import:DR127")
      (libsource (lib "eagle-import") (part "DR127"))
    )
    (comp (ref "L7")
      (value "DR127")
      (footprint "eagle-import:DR127")
      (libsource (lib "eagle-import") (part "DR127"))
    )
    (comp (ref "L101")
      (value "1uH")
      (footprint "eagle-import:L1008")
      (fields (field (name "PARTNO") "1008CS-102XJEC"))
      (libsource (lib "eagle-import") (part "L_CHIP1008L-1.0U-AIR-5%-1008-0.37A"))
    )
    (comp (ref "L102")
      (value "1uH")
      (footprint "eagle-import:L1008")
      (fields (field (name "PARTNO") "1008CS-102XJEC"))
      (libsource (lib "eagle-import") (part "L_CHIP1008L-1.0U-AIR-5%-1008-0.37A"))
    )
    (comp (ref "Q101")
      (value "IRF540")
      (footprint "eagle-import:TO220BV")
      (libsource (lib "eagle-import") (part "IRF540"))
    )
    (comp (ref "Q102")
      (value "IRF540")
      (footprint "eagle-import:TO220BV")
      (libsource (lib "eagle-import") (part "IRF540"))
    )
    (comp (ref "R30")
      (value "1.0K")
      (footprint "eagle-import:0805_IPC-7351B")
      (libsource (lib "eagle-import") (part "R0805_IPCR-1.0K-0.1%-0805-0.1W"))
    )
    (comp (ref "R31")
      (value "1.0K")
      (footprint "eagle-import:0805_IPC-7351B")
      (libsource (lib "eagle-import") (part "R0805_IPCR-1.0K-0.1%-0805-0.1W"))
    )
    (comp (ref "R32")
      (value "1K")
      (footprint "eagle-import:R2512")
      (fields (field (name "POWER") "1"))
      (libsource (lib "eagle-import") (part "RR2512R-1K-1%-2512-1W"))
    )
    (comp (ref "R33")
      (value "1K")
      (footprint "eagle-import:R2512")
      (fields (field (name "POWER") "1"))
      (libsource (lib "eagle-import") (part "RR2512R-1K-1%-2512-1W"))
    )
    (comp (ref "R34")
      (value "1K")
      (footprint "eagle-import:R2512")
      (fields (field (name "POWER") "1"))
      (libsource (lib "eagle-import") (part "RR2512R-1K-1%-2512-1W"))
    )
    (comp (ref "R35")
      (value "1K")
      (footprint "eagle-import:R2512")
      (fields (field (name "POWER") "1"))
      (libsource (lib "eagle-import") (part "RR2512R-1K-1%-2512-1W"))
    )
    (comp (ref "R101")
      (value "1K")
      (footprint "eagle-import:R1206")
      (fields (field (name "POWER") "0.25"))
      (libsource (lib "eagle-import") (part "RR1206R-1.0K-1%-1206-0.25W"))
    )
    (comp (ref "R102")
      (value "1K")
      (footprint "eagle-import:R1206")
      (fields (field (name "POWER") "0.25"))
      (libsource (lib "eagle-import") (part "RR1206R-1.0K-1%-1206-0.25W"))
    )
    (comp (ref "R103")
      (value "1K")
      (footprint "eagle-import:R1206")
      (fields (field (name "POWER") "0.25"))
      (libsource (lib "eagle-import") (part "RR1206R-1.0K-1%-1206-0.25W"))
    )
    (comp (ref "R104")
      (value "1K")
      (footprint "eagle-import:R1206")
      (fields (field (name "POWER") "0.25"))
      (libsource (lib "eagle-import") (part "RR1206R-1.0K-1%-1206-0.25W"))
    )
    (comp (ref "R105")
      (value "1K")
      (footprint "eagle-import:R1206")
      (fields (field (name "POWER") "0.25"))
      (libsource (lib "eagle-import") (part "RR1206R-1.0K-1%-1206-0.25W"))
    )
    (comp (ref "R106")
      (value "1K")
      (footprint "eagle-import:R1206")
      (fields (field (name "POWER") "0.25"))
      (libsource (lib "eagle-import") (part "RR1206R-1.0K-1%-1206-0.25W"))
    )
    (comp (ref "R107")
      (value "1.0K")
      (footprint "eagle-import:0805_IPC-7351B")
      (libsource (lib "eagle-import") (part "R0805_IPCR-1.0K-0.1%-0805-0.1W"))
    )
    (comp (ref "R108")
      (value "1K")
      (footprint "eagle-import:R1206")
      (fields (field (name "POWER") "0.25"))
      (libsource (lib "eagle-import") (part "RR1206R-1.0K-1%-1206-0.25W"))
    )
    (comp (ref "R109")
      (value "1.0K")
      (footprint "eagle-import:0805_IPC-7351B")
      (libsource (lib "eagle-import") (part "R0805_IPCR-1.0K-0.1%-0805-0.1W"))
    )
    (comp (ref "R110")
      (value "1K")
      (footprint "eagle-import:R1206")
      (fields (field (name "POWER") "0.25"))
      (libsource (lib "eagle-import") (part "RR1206R-1.0K-1%-1206-0.25W"))
    )
    (comp (ref "R111")
      (value "1.0K")
      (footprint "eagle-import:0805_IPC-7351B")
      (libsource (lib "eagle-import") (part "R0805_IPCR-1.0K-0.1%-0805-0.1W"))
    )
    (comp (ref "R112")
      (value "1.0K")
      (footprint "eagle-import:0805_IPC-7351B")
      (libsource (lib "eagle-import") (part "R0805_IPCR-1.0K-0.1%-0805-0.1W"))
    )
    (comp (ref "R113")
      (value "1.0K")
      (footprint "eagle-import:0805_IPC-7351B")
      (libsource (lib "eagle-import") (part "R0805_IPCR-1.0K-0.1%-0805-0.1W"))
    )
    (comp (ref "R114")
      (value "1.0K")
      (footprint "eagle-import:0805_IPC-7351B")
      (libsource (lib "eagle-import") (part "R0805_IPCR-1.0K-0.1%-0805-0.1W"))
    )
    (comp (ref "R115")
      (value "1.0K")
      (footprint "eagle-import:0805_IPC-7351B")
      (libsource (lib "eagle-import") (part "R0805_IPCR-1.0K-0.1%-0805-0.1W"))
    )
    (comp (ref "R116")
      (value "1.0K")
      (footprint "eagle-import:0805_IPC-7351B")
      (libsource (lib "eagle-import") (part "R0805_IPCR-1.0K-0.1%-0805-0.1W"))
    )
    (comp (ref "R117")
      (value "1K")
      (footprint "eagle-import:R2512")
      (fields (field (name "POWER") "1"))
      (libsource (lib "eagle-import") (part "RR2512R-1K-1%-2512-1W"))
    )
    (comp (ref "R118")
      (value "1K")
      (footprint "eagle-import:R2512")
      (fields (field (name "POWER") "1"))
      (libsource (lib "eagle-import") (part "RR2512R-1K-1%-2512-1W"))
    )
    (comp (ref "R119")
      (value "1K")
      (footprint "eagle-import:R2512")
      (fields (field (name "POWER") "1"))
      (libsource (lib "eagle-import") (part "RR2512R-1K-1%-2512-1W"))
    )
    (comp (ref "R120")
      (value "1K")
      (footprint "eagle-import:R2512")
      (fields (field (name "POWER") "1"))
      (libsource (lib "eagle-import") (part "RR2512R-1K-1%-2512-1W"))
    )
    (comp (ref "R121")
      (value "1K")
      (footprint "eagle-import:R2512")
      (fields (field (name "POWER") "1"))
      (libsource (lib "eagle-import") (part "RR2512R-1K-1%-2512-1W"))
    )
    (comp (ref "R122")
      (value "1K")
      (footprint "eagle-import:R2512")
      (fields (field (name "POWER") "1"))
      (libsource (lib "eagle-import") (part "RR2512R-1K-1%-2512-1W"))
    )
    (comp (ref "R123")
      (value "1K")
      (footprint "eagle-import:R2512")
      (fields (field (name "POWER") "1"))
      (libsource (lib "eagle-import") (part "RR2512R-1K-1%-2512-1W"))
    )
    (comp (ref "R124")
      (value "1K")
      (footprint "eagle-import:R2512")
      (fields (field (name "POWER") "1"))
      (libsource (lib "eagle-import") (part "RR2512R-1K-1%-2512-1W"))
    )
    (comp (ref "R125")
      (value "1.0K")
      (footprint "eagle-import:0805_IPC-7351B")
      (libsource (lib "eagle-import") (part "R0805_IPCR-1.0K-0.1%-0805-0.1W"))
    )
    (comp (ref "R126")
      (value "1.0K")
      (footprint "eagle-import:0805_IPC-7351B")
      (libsource (lib "eagle-import") (part "R0805_IPCR-1.0K-0.1%-0805-0.1W"))
    )
    (comp (ref "T1")
      (value "HP4_TRAFO")
      (footprint "eagle-import:HP4")
      (libsource (lib "eagle-import") (part "HP4_TRAFO"))
    )
    (comp (ref "T2")
      (value "HP4_TRAFO")
      (footprint "eagle-import:HP4")
      (libsource (lib "eagle-import") (part "HP4_TRAFO"))
    )
    (comp (ref "TP1")
      (value "PROBE_TPTP_5MM")
      (footprint "eagle-import:PROBE_TP_5MM")
      (libsource (lib "eagle-import") (part "PROBE_TPTP_5MM"))
    )
    (comp (ref "TP2")
      (value "PROBE_TPTP_7P5MM")
      (footprint "eagle-import:PROBE_TP_7P5MM")
      (libsource (lib "eagle-import") (part "PROBE_TPTP_7P5MM"))
    )
    (comp (ref "TP3")
      (value "PROBE_TPTP_5MM")
      (footprint "eagle-import:PROBE_TP_5MM")
      (libsource (lib "eagle-import") (part "PROBE_TPTP_5MM"))
    )
    (comp (ref "TP4")
      (value "PROBE_TPTP_7P5MM")
      (footprint "eagle-import:PROBE_TP_7P5MM")
      (libsource (lib "eagle-import") (part "PROBE_TPTP_7P5MM"))
    )
    (comp (ref "TP5")
      (value "PROBE_TPTP_7P5MM")
      (footprint "eagle-import:PROBE_TP_7P5MM")
      (libsource (lib "eagle-import") (part "PROBE_TPTP_7P5MM"))
    )
    (comp (ref "TP6")
      (value "PROBE_TPTP_7P5MM")
      (footprint "eagle-import:PROBE_TP_7P5MM")
      (libsource (lib "eagle-import") (part "PROBE_TPTP_7P5MM"))
    )
    (comp (ref "TP14")
      (value "PROBE_TPTP_5MM")
      (footprint "eagle-import:PROBE_TP_5MM")
      (libsource (lib "eagle-import") (part "PROBE_TPTP_5MM"))
    )
    (comp (ref "TP15")
      (value "PROBE_TPTP_5MM")
      (footprint "eagle-import:PROBE_TP_5MM")
      (libsource (lib "eagle-import") (part "PROBE_TPTP_5MM"))
    )
    (comp (ref "TP18")
      (value "PROBE_TPTP_5MM")
      (footprint "eagle-import:PROBE_TP_5MM")
      (libsource (lib "eagle-import") (part "PROBE_TPTP_5MM"))
    )
    (comp (ref "TP19")
      (value "PROBE_TPTP_5MM")
      (footprint "eagle-import:PROBE_TP_5MM")
      (libsource (lib "eagle-import") (part "PROBE_TPTP_5MM"))
    )
  )
  (nets
    (net (code "1") (name "+5V") (class "Default")
      (node (ref "C16") (pin "1") (pinfunction "1_1") (pintype "passive"))
      (node (ref "C22") (pin "1") (pinfunction "1_1") (pintype "passive"))
      (node (ref "IC201") (pin "5") (pinfunction "VCC_5") (pintype "power_in"))
      (node (ref "IC302") (pin "OUT") (pinfunction "OUT_OUT") (pintype "passive"))
      (node (ref "LED1") (pin "A") (pinfunction "A_A") (pintype "passive"))
      (node (ref "LED3") (pin "A") (pinfunction "A_A") (pintype "passive"))
      (node (ref "R201") (pin "3") (pinfunction "E_3") (pintype "passive"))
      (node (ref "R29") (pin "1") (pinfunction "1_1") (pintype "passive"))
    )
    (net (code "2") (name "+12V") (class "Default")
      (node (ref "C15") (pin "1") (pinfunction "1_1") (pintype "passive"))
      (node (ref "C210") (pin "1") (pinfunction "1_1") (pintype "passive"))
      (node (ref "IC202") (pin "4") (pinfunction "V+_4") (pintype "power_in"))
      (node (ref "IC301") (pin "OUT") (pinfunction "OUT_OUT") (pintype "passive"))
      (node (ref "J2") (pin "2") (pinfunction "2_2") (pintype "passive"))
      (node (ref "LED2") (pin "A") (pinfunction "A_A") (pintype "passive"))
      (node (ref "T201") (pin "C") (pinfunction "C_C") (pintype "passive"))
    )
    (net (code "3") (name "ABN1") (class "Default")
      (node (ref "R101") (pin "1") (pinfunction "1_1") (pintype "passive"))
      (node (ref "R103") (pin "1") (pinfunction "1_1") (pintype "passive"))
      (node (ref "R13") (pin "1") (pinfunction "1_1") (pintype "passive"))
      (node (ref "R6") (pin "1") (pinfunction "1_1") (pintype "passive"))
      (node (ref "T1") (pin "11") (pinfunction "F2_11") (pintype "passive"))
      (node (ref "TP18") (pin "TP") (pinfunction "1_TP") (pintype "passive"))
    )
    (net (code "4") (name "ABP1") (class "Default")
      (node (ref "R102") (pin "1") (pinfunction "1_1") (pintype "passive"))
      (node (ref "R104") (pin "1") (pinfunction "1_1") (pintype "passive"))
      (node (ref "R19") (pin "1") (pinfunction "1_1") (pintype "passive"))
      (node (ref "R26") (pin "1") (pinfunction "1_1") (pintype "passive"))
      (node (ref "T1") (pin "1") (pinfunction "S1_1") (pintype "passive"))
      (node (ref "TP19") (pin "TP") (pinfunction "1_TP") (pintype "passive"))
    )
    (net (code "5") (name "AN2") (class "Default")
      (node (ref "C103") (pin "2") (pinfunction "2_2") (pintype "passive"))
      (node (ref "R103") (pin "2") (pinfunction "2_2") (pintype "passive"))
      (node (ref "R105") (pin "1") (pinfunction "1_1") (pintype "passive"))
    )
    (net (code "6") (name "AN3") (class "Default")
      (node (ref "C103") (pin "1") (pinfunction "1_1") (pintype "passive"))
      (node (ref "L101") (pin "1") (pinfunction "1_1") (pintype "passive"))
      (node (ref "R108") (pin "2") (pinfunction "2_2") (pintype "passive"))
      (node (ref "R111") (pin "1") (pinfunction "1_1") (pintype "passive"))
      (node (ref "R113") (pin "1") (pinfunction "1_1") (pintype "passive"))
    )
    (net (code "7") (name "AN4") (class "Default")
      (node (ref "L101") (pin "2") (pinfunction "2_2") (pintype "passive"))
      (node (ref "Q101") (pin "G") (pinfunction "G_G") (pintype "passive"))
      (node (ref "R113") (pin "2") (pinfunction "2_2") (pintype "passive"))
      (node (ref "R115") (pin "1") (pinfunction "1_1") (pintype "passive"))
      (node (ref "R117") (pin "1") (pinfunction "1_1") (pintype "passive"))
      (node (ref "R118") (pin "1") (pinfunction "1_1") (pintype "passive"))
      (node (ref "TP3") (pin "TP") (pinfunction "1_TP") (pintype "passive"))
    )
    (net (code "8") (name "AN5") (class "Default")
      (node (ref "Q101") (pin "S") (pinfunction "S_S") (pintype "passive"))
      (node (ref "R121") (pin "1") (pinfunction "1_1") (pintype "passive"))
      (node (ref "R123") (pin "1") (pinfunction "1_1") (pintype "passive"))
      (node (ref "R125") (pin "1") (pinfunction "1_1") (pintype "passive"))
      (node (ref "R34") (pin "1") (pinfunction "1_1") (pintype "passive"))
      (node (ref "R35") (pin "1") (pinfunction "1_1") (pintype "passive"))
      (node (ref "TP6") (pin "TP") (pinfunction "1_TP") (pintype "passive"))
    )
    (net (code "9") (name "AN6") (class "Default")
      (node (ref "C113") (pin "1") (pinfunction "1_1") (pintype "passive"))
      (node (ref "R125") (pin "2") (pinfunction "2_2") (pintype "passive"))
      (node (ref "TP15") (pin "TP") (pinfunction "1_TP") (pintype "passive"))
    )
    (net (code "10") (name "AP2") (class "Default")
      (node (ref "C105") (pin "2") (pinfunction "2_2") (pintype "passive"))
      (node (ref "R104") (pin "2") (pinfunction "2_2") (pintype "passive"))
      (node (ref "R106") (pin "1") (pinfunction "1_1") (pintype "passive"))
    )
    (net (code "11") (name "AP3") (class "Default")
      (node (ref "C105") (pin "1") (pinfunction "1_1") (pintype "passive"))
      (node (ref "L102") (pin "1") (pinfunction "1_1") (pintype "passive"))
      (node (ref "R110") (pin "2") (pinfunction "2_2") (pintype "passive"))
      (node (ref "R112") (pin "1") (pinfunction "1_1") (pintype "passive"))
      (node (ref "R114") (pin "1") (pinfunction "1_1") (pintype "passive"))
    )
    (net (code "12") (name "AP4") (class "Default")
      (node (ref "L102") (pin "2") (pinfunction "2_2") (pintype "passive"))
      (node (ref "Q102") (pin "G") (pinfunction "G_G") (pintype "passive"))
      (node (ref "R114") (pin "2") (pinfunction "2_2") (pintype "passive"))
      (node (ref "R116") (pin "1") (pinfunction "1_1") (pintype "passive"))
      (node (ref "R119") (pin "1") (pinfunction "1_1") (pintype "passive"))
      (node (ref "R120") (pin "1") (pinfunction "1_1") (pintype "passive"))
      (node (ref "TP1") (pin "TP") (pinfunction "1_TP") (pintype "passive"))
    )
    (net (code "13") (name "AP5") (class "Default")
      (node (ref "Q102") (pin "S") (pinfunction "S_S") (pintype "passive"))
      (node (ref "R122") (pin "1") (pinfunction "1_1") (pintype "passive"))
      (node (ref "R124") (pin "1") (pinfunction "1_1") (pintype "passive"))
      (node (ref "R126") (pin "1") (pinfunction "1_1") (pintype "passive"))
      (node (ref "R32") (pin "1") (pinfunction "1_1") (pintype "passive"))
      (node (ref "R33") (pin "1") (pinfunction "1_1") (pintype "passive"))
      (node (ref "TP5") (pin "TP") (pinfunction "1_TP") (pintype "passive"))
    )
    (net (code "14") (name "AP6") (class "Default")
      (node (ref "C114") (pin "1") (pinfunction "1_1") (pintype "passive"))
      (node (ref "R126") (pin "2") (pinfunction "2_2") (pintype "passive"))
      (node (ref "TP14") (pin "TP") (pinfunction "1_TP") (pintype "passive"))
    )
    (net (code "15") (name "BN2") (class "Default")
      (node (ref "C5") (pin "2") (pinfunction "2_2") (pintype "passive"))
      (node (ref "R5") (pin "1") (pinfunction "1_1") (pintype "passive"))
      (node (ref "R6") (pin "2") (pinfunction "2_2") (pintype "passive"))
    )
    (net (code "16") (name "BN3") (class "Default")
      (node (ref "C5") (pin "1") (pinfunction "1_1") (pintype "passive"))
      (node (ref "L1") (pin "1") (pinfunction "1_1") (pintype "passive"))
      (node (ref "R4") (pin "2") (pinfunction "2_2") (pintype "passive"))
      (node (ref "R8") (pin "1") (pinfunction "1_1") (pintype "passive"))
      (node (ref "R9") (pin "1") (pinfunction "1_1") (pintype "passive"))
    )
    (net (code "17") (name "BN4") (class "Default")
      (node (ref "L1") (pin "2") (pinfunction "2_2") (pintype "passive"))
      (node (ref "Q2") (pin "G") (pinfunction "G_G") (pintype "passive"))
      (node (ref "R1") (pin "1") (pinfunction "1_1") (pintype "passive"))
      (node (ref "R10") (pin "1") (pinfunction "1_1") (pintype "passive"))
      (node (ref "R7") (pin "1") (pinfunction "1_1") (pintype "passive"))
      (node (ref "R8") (pin "2") (pinfunction "2_2") (pintype "passive"))
      (node (ref "TP9") (pin "TP") (pinfunction "1_TP") (pintype "passive"))
    )
    (net (code "18") (name "BN5") (class "Default")
      (node (ref "Q2") (pin "S") (pinfunction "S_S") (pintype "passive"))
      (node (ref "R11") (pin "1") (pinfunction "1_1") (pintype "passive"))
      (node (ref "R2") (pin "1") (pinfunction "1_1") (pintype "passive"))
      (node (ref "R3") (pin "1") (pinfunction "1_1") (pintype "passive"))
      (node (ref "R36") (pin "1") (pinfunction "1_1") (pintype "passive"))
      (node (ref "R37") (pin "1") (pinfunction "1_1") (pintype "passive"))
      (node (ref "TP10") (pin "TP") (pinfunction "1_TP") (pintype "passive"))
    )
    (net (code "19") (name "BN6") (class "Default")
      (node (ref "C2") (pin "1") (pinfunction "1_1") (pintype "passive"))
      (node (ref "R11") (pin "2") (pinfunction "2_2") (pintype "passive"))
      (node (ref "TP17") (pin "TP") (pinfunction "1_TP") (pintype "passive"))
    )
    (net (code "20") (name "BP2") (class "Default")
      (node (ref "C11") (pin "2") (pinfunction "2_2") (pintype "passive"))
      (node (ref "R18") (pin "1") (pinfunction "1_1") (pintype "passive"))
      (node (ref "R19") (pin "2") (pinfunction "2_2") (pintype "passive"))
    )
    (net (code "21") (name "BP3") (class "Default")
      (node (ref "C11") (pin "1") (pinfunction "1_1") (pintype "passive"))
      (node (ref "L2") (pin "1") (pinfunction "1_1") (pintype "passive"))
      (node (ref "R17") (pin "2") (pinfunction "2_2") (pintype "passive"))
      (node (ref "R21") (pin "1") (pinfunction "1_1") (pintype "passive"))
      (node (ref "R22") (pin "1") (pinfunction "1_1") (pintype "passive"))
    )
    (net (code "22") (name "BP4") (class "Default")
      (node (ref "L2") (pin "2") (pinfunction "2_2") (pintype "passive"))
      (node (ref "Q1") (pin "G") (pinfunction "G_G") (pintype "passive"))
      (node (ref "R14") (pin "1") (pinfunction "1_1") (pintype "passive"))
      (node (ref "R20") (pin "1") (pinfunction "1_1") (pintype "passive"))
      (node (ref "R21") (pin "2") (pinfunction "2_2") (pintype "passive"))
      (node (ref "R23") (pin "1") (pinfunction "1_1") (pintype "passive"))
      (node (ref "TP7") (pin "TP") (pinfunction "1_TP") (pintype "passive"))
    )
    (net (code "23") (name "BP5") (class "Default")
      (node (ref "Q1") (pin "S") (pinfunction "S_S") (pintype "passive"))
      (node (ref "R15") (pin "1") (pinfunction "1_1") (pintype "passive"))
      (node (ref "R16") (pin "1") (pinfunction "1_1") (pintype "passive"))
      (node (ref "R24") (pin "1") (pinfunction "1_1") (pintype "passive"))
      (node (ref "R38") (pin "1") (pinfunction "1_1") (pintype "passive"))
      (node (ref "R39") (pin "1") (pinfunction "1_1") (pintype "passive"))
      (node (ref "TP8") (pin "TP") (pinfunction "1_TP") (pintype "passive"))
    )
    (net (code "24") (name "BP6") (class "Default")
      (node (ref "C8") (pin "1") (pinfunction "1_1") (pintype "passive"))
      (node (ref "R24") (pin "2") (pinfunction "2_2") (pintype "passive"))
      (node (ref "TP16") (pin "TP") (pinfunction "1_TP") (pintype "passive"))
    )
    (net (code "25") (name "DRAINS_NEG") (class "Default")
      (node (ref "C1") (pin "2") (pinfunction "2_2") (pintype "passive"))
      (node (ref "C111") (pin "2") (pinfunction "2_2") (pintype "passive"))
      (node (ref "C18") (pin "2") (pinfunction "2_2") (pintype "passive"))
      (node (ref "L7") (pin "1") (pinfunction "1_1") (pintype "passive"))
      (node (ref "Q101") (pin "D") (pinfunction "D_D") (pintype "passive"))
      (node (ref "Q2") (pin "D") (pinfunction "D_D") (pintype "passive"))
      (node (ref "T2") (pin "8") (pinfunction "F5_8") (pintype "passive"))
      (node (ref "TP4") (pin "TP") (pinfunction "1_TP") (pintype "passive"))
    )
    (net (code "26") (name "DRAINS_POS") (class "Default")
      (node (ref "C112") (pin "2") (pinfunction "2_2") (pintype "passive"))
      (node (ref "C17") (pin "2") (pinfunction "2_2") (pintype "passive"))
      (node (ref "C7") (pin "2") (pinfunction "2_2") (pintype "passive"))
      (node (ref "L6") (pin "1") (pinfunction "1_1") (pintype "passive"))
      (node (ref "Q1") (pin "D") (pinfunction "D_D") (pintype "passive"))
      (node (ref "Q102") (pin "D") (pinfunction "D_D") (pintype "passive"))
      (node (ref "T2") (pin "6") (pinfunction "S6_6") (pintype "passive"))
      (node (ref "TP2") (pin "TP") (pinfunction "1_TP") (pintype "passive"))
    )
    (net (code "27") (name "GBIAS") (class "Default")
      (node (ref "R107") (pin "1") (pinfunction "1_1") (pintype "passive"))
      (node (ref "R109") (pin "1") (pinfunction "1_1") (pintype "passive"))
      (node (ref "R12") (pin "1") (pinfunction "1_1") (pintype "passive"))
      (node (ref "R218") (pin "2") (pinfunction "2_2") (pintype "passive"))
      (node (ref "R219") (pin "2") (pinfunction "2_2") (pintype "passive"))
      (node (ref "R25") (pin "1") (pinfunction "1_1") (pintype "passive"))
      (node (ref "T201") (pin "E") (pinfunction "E_E") (pintype "passive"))
      (node (ref "T202") (pin "E") (pinfunction "E_E") (pintype "passive"))
      (node (ref "TP11") (pin "TP") (pinfunction "1_TP") (pintype "passive"))
    )
    (net (code "28") (name "GND") (class "Default")
      (node (ref "C10") (pin "2") (pinfunction "2_2") (pintype "passive"))
      (node (ref "C102") (pin "2") (pinfunction "2_2") (pintype "passive"))
      (node (ref "C104") (pin "2") (pinfunction "2_2") (pintype "passive"))
      (node (ref "C106") (pin "2") (pinfunction "2_2") (pintype "passive"))
      (node (ref "C107") (pin "2") (pinfunction "2_2") (pintype "passive"))
      (node (ref "C109") (pin "2") (pinfunction "2_2") (pintype "passive"))
      (node (ref "C110") (pin "2") (pinfunction "2_2") (pintype "passive"))
      (node (ref "C113") (pin "2") (pinfunction "2_2") (pintype "passive"))
      (node (ref "C114") (pin "2") (pinfunction "2_2") (pintype "passive"))
      (node (ref "C12") (pin "2") (pinfunction "2_2") (pintype "passive"))
      (node (ref "C13") (pin "2") (pinfunction "2_2") (pintype "passive"))
      (node (ref "C14") (pin "2") (pinfunction "2_2") (pintype "passive"))
      (node (ref "C15") (pin "2") (pinfunction "2_2") (pintype "passive"))
      (node (ref "C16") (pin "2") (pinfunction "2_2") (pintype "passive"))
      (node (ref "C19") (pin "2") (pinfunction "2_2") (pintype "passive"))
      (node (ref "C2") (pin "2") (pinfunction "2_2") (pintype "passive"))
      (node (ref "C20") (pin "2") (pinfunction "2_2") (pintype "passive"))
      (node (ref "C201") (pin "2") (pinfunction "2_2") (pintype "passive"))
      (node (ref "C207") (pin "2") (pinfunction "2_2") (pintype "passive"))
      (node (ref "C208") (pin "2") (pinfunction "2_2") (pintype "passive"))
      (node (ref "C21") (pin "2") (pinfunction "2_2") (pintype "passive"))
      (node (ref "C210") (pin "2") (pinfunction "2_2") (pintype "passive"))
      (node (ref "C22") (pin "2") (pinfunction "2_2") (pintype "passive"))
      (node (ref "C23") (pin "2") (pinfunction "2_2") (pintype "passive"))
      (node (ref "C3") (pin "2") (pinfunction "2_2") (pintype "passive"))
      (node (ref "C301") (pin "-") (pinfunction "-_-") (pintype "passive"))
      (node (ref "C303") (pin "2") (pinfunction "2_2") (pintype "passive"))
      (node (ref "C304") (pin "2") (pinfunction "2_2") (pintype "passive"))
      (node (ref "C4") (pin "2") (pinfunction "2_2") (pintype "passive"))
      (node (ref "C6") (pin "2") (pinfunction "2_2") (pintype "passive"))
      (node (ref "C8") (pin "2") (pinfunction "2_2") (pintype "passive"))
      (node (ref "C9") (pin "2") (pinfunction "2_2") (pintype "passive"))
      (node (ref "D301") (pin "A") (pinfunction "A_A") (pintype "passive"))
      (node (ref "H1") (pin "B3,2") (pinfunction "MOUNT_B3,2") (pintype "passive"))
      (node (ref "H2") (pin "B3,2") (pinfunction "MOUNT_B3,2") (pintype "passive"))
      (node (ref "H3") (pin "B3,2") (pinfunction "MOUNT_B3,2") (pintype "passive"))
      (node (ref "H4") (pin "B3,2") (pinfunction "MOUNT_B3,2") (pintype "passive"))
      (node (ref "IC201") (pin "3") (pinfunction "GND_3") (pintype "power_in"))
      (node (ref "IC202") (pin "11") (pinfunction "V-_11") (pintype "power_in"))
      (node (ref "IC301") (pin "GND") (pinfunction "GND_GND") (pintype "input"))
      (node (ref "IC302") (pin "GND") (pinfunction "GND_GND") (pintype "input"))
      (node (ref "J101") (pin "G1") (pinfunction "GND1_G1") (pintype "power_in"))
      (node (ref "J101") (pin "G2") (pinfunction "GND1_G2") (pintype "power_in"))
      (node (ref "J101") (pin "G3") (pinfunction "GND1_G3") (pintype "power_in"))
      (node (ref "J101") (pin "G4") (pinfunction "GND1_G4") (pintype "power_in"))
      (node (ref "J102") (pin "G1") (pinfunction "GND1_G1") (pintype "power_in"))
      (node (ref "J102") (pin "G2") (pinfunction "GND1_G2") (pintype "power_in"))
      (node (ref "J102") (pin "G3") (pinfunction "GND1_G3") (pintype "power_in"))
      (node (ref "J102") (pin "G4") (pinfunction "GND1_G4") (pintype "power_in"))
      (node (ref "J2") (pin "1") (pinfunction "1_1") (pintype "passive"))
      (node (ref "J202") (pin "G1") (pinfunction "GND1_G1") (pintype "power_in"))
      (node (ref "J202") (pin "G2") (pinfunction "GND1_G2") (pintype "power_in"))
      (node (ref "J202") (pin "G3") (pinfunction "GND1_G3") (pintype "power_in"))
      (node (ref "J202") (pin "G4") (pinfunction "GND1_G4") (pintype "power_in"))
      (node (ref "Q201") (pin "2") (pinfunction "S_2") (pintype "passive"))
      (node (ref "R101") (pin "2") (pinfunction "2_2") (pintype "passive"))
      (node (ref "R102") (pin "2") (pinfunction "2_2") (pintype "passive"))
      (node (ref "R105") (pin "2") (pinfunction "2_2") (pintype "passive"))
      (node (ref "R106") (pin "2") (pinfunction "2_2") (pintype "passive"))
      (node (ref "R121") (pin "2") (pinfunction "2_2") (pintype "passive"))
      (node (ref "R122") (pin "2") (pinfunction "2_2") (pintype "passive"))
      (node (ref "R123") (pin "2") (pinfunction "2_2") (pintype "passive"))
      (node (ref "R124") (pin "2") (pinfunction "2_2") (pintype "passive"))
      (node (ref "R13") (pin "2") (pinfunction "2_2") (pintype "passive"))
      (node (ref "R15") (pin "2") (pinfunction "2_2") (pintype "passive"))
      (node (ref "R16") (pin "2") (pinfunction "2_2") (pintype "passive"))
      (node (ref "R18") (pin "2") (pinfunction "2_2") (pintype "passive"))
      (node (ref "R2") (pin "2") (pinfunction "2_2") (pintype "passive"))
      (node (ref "R201") (pin "1") (pinfunction "A_1") (pintype "passive"))
      (node (ref "R204") (pin "2") (pinfunction "2_2") (pintype "passive"))
      (node (ref "R211") (pin "2") (pinfunction "2_2") (pintype "passive"))
      (node (ref "R212") (pin "1") (pinfunction "1_1") (pintype "passive"))
      (node (ref "R26") (pin "2") (pinfunction "2_2") (pintype "passive"))
      (node (ref "R27") (pin "2") (pinfunction "2_2") (pintype "passive"))
      (node (ref "R28") (pin "2") (pinfunction "2_2") (pintype "passive"))
      (node (ref "R3") (pin "2") (pinfunction "2_2") (pintype "passive"))
      (node (ref "R31") (pin "2") (pinfunction "2_2") (pintype "passive"))
      (node (ref "R32") (pin "2") (pinfunction "2_2") (pintype "passive"))
      (node (ref "R33") (pin "2") (pinfunction "2_2") (pintype "passive"))
      (node (ref "R34") (pin "2") (pinfunction "2_2") (pintype "passive"))
      (node (ref "R35") (pin "2") (pinfunction "2_2") (pintype "passive"))
      (node (ref "R36") (pin "2") (pinfunction "2_2") (pintype "passive"))
      (node (ref "R37") (pin "2") (pinfunction "2_2") (pintype "passive"))
      (node (ref "R38") (pin "2") (pinfunction "2_2") (pintype "passive"))
      (node (ref "R39") (pin "2") (pinfunction "2_2") (pintype "passive"))
      (node (ref "R5") (pin "2") (pinfunction "2_2") (pintype "passive"))
      (node (ref "T1") (pin "10") (pinfunction "F3_10") (pintype "passive"))
      (node (ref "T2") (pin "9") (pinfunction "F4_9") (pintype "passive"))
      (node (ref "T202") (pin "C") (pinfunction "C_C") (pintype "passive"))
      (node (ref "TP1") (pin "GND") (pinfunction "GND1_GND") (pintype "power_in"))
      (node (ref "TP10") (pin "GND") (pinfunction "GND1_GND") (pintype "power_in"))
      (node (ref "TP11") (pin "GND") (pinfunction "GND1_GND") (pintype "power_in"))
      (node (ref "TP12") (pin "GND") (pinfunction "GND1_GND") (pintype "power_in"))
      (node (ref "TP13") (pin "GND") (pinfunction "GND1_GND") (pintype "power_in"))
      (node (ref "TP14") (pin "GND") (pinfunction "GND1_GND") (pintype "power_in"))
      (node (ref "TP15") (pin "GND") (pinfunction "GND1_GND") (pintype "power_in"))
      (node (ref "TP16") (pin "GND") (pinfunction "GND1_GND") (pintype "power_in"))
      (node (ref "TP17") (pin "GND") (pinfunction "GND1_GND") (pintype "power_in"))
      (node (ref "TP18") (pin "GND") (pinfunction "GND1_GND") (pintype "power_in"))
      (node (ref "TP19") (pin "GND") (pinfunction "GND1_GND") (pintype "power_in"))
      (node (ref "TP2") (pin "GND") (pinfunction "GND1_GND") (pintype "power_in"))
      (node (ref "TP3") (pin "GND") (pinfunction "GND1_GND") (pintype "power_in"))
      (node (ref "TP4") (pin "GND") (pinfunction "GND1_GND") (pintype "power_in"))
      (node (ref "TP5") (pin "GND") (pinfunction "GND1_GND") (pintype "power_in"))
      (node (ref "TP6") (pin "GND") (pinfunction "GND1_GND") (pintype "power_in"))
      (node (ref "TP7") (pin "GND") (pinfunction "GND1_GND") (pintype "power_in"))
      (node (ref "TP8") (pin "GND") (pinfunction "GND1_GND") (pintype "power_in"))
      (node (ref "TP9") (pin "GND") (pinfunction "GND1_GND") (pintype "power_in"))
      (node (ref "X1") (pin "2") (pinfunction "KL_2") (pintype "passive"))
      (node (ref "X101") (pin "P1") (pinfunction "P$1_P1") (pintype "bidirectional"))
      (node (ref "X101") (pin "P2") (pinfunction "P$2_P2") (pintype "bidirectional"))
    )
    (net (code "29") (name "Net-(C1-Pad1)") (class "Default")
      (node (ref "C1") (pin "1") (pinfunction "1_1") (pintype "passive"))
      (node (ref "R1") (pin "2") (pinfunction "2_2") (pintype "passive"))
      (node (ref "R7") (pin "2") (pinfunction "2_2") (pintype "passive"))
    )
    (net (code "30") (name "Net-(C3-Pad1)") (class "Default")
      (node (ref "C3") (pin "1") (pinfunction "1_1") (pintype "passive"))
      (node (ref "R10") (pin "2") (pinfunction "2_2") (pintype "passive"))
    )
    (net (code "31") (name "Net-(C4-Pad1)") (class "Default")
      (node (ref "C4") (pin "1") (pinfunction "1_1") (pintype "passive"))
      (node (ref "R9") (pin "2") (pinfunction "2_2") (pintype "passive"))
    )
    (net (code "32") (name "Net-(C6-Pad1)") (class "Default")
      (node (ref "C6") (pin "1") (pinfunction "1_1") (pintype "passive"))
      (node (ref "R12") (pin "2") (pinfunction "2_2") (pintype "passive"))
      (node (ref "R4") (pin "1") (pinfunction "1_1") (pintype "passive"))
    )
    (net (code "33") (name "Net-(C7-Pad1)") (class "Default")
      (node (ref "C7") (pin "1") (pinfunction "1_1") (pintype "passive"))
      (node (ref "R14") (pin "2") (pinfunction "2_2") (pintype "passive"))
      (node (ref "R20") (pin "2") (pinfunction "2_2") (pintype "passive"))
    )
    (net (code "34") (name "Net-(C9-Pad1)") (class "Default")
      (node (ref "C9") (pin "1") (pinfunction "1_1") (pintype "passive"))
      (node (ref "R23") (pin "2") (pinfunction "2_2") (pintype "passive"))
    )
    (net (code "35") (name "Net-(C10-Pad1)") (class "Default")
      (node (ref "C10") (pin "1") (pinfunction "1_1") (pintype "passive"))
      (node (ref "R22") (pin "2") (pinfunction "2_2") (pintype "passive"))
    )
    (net (code "36") (name "Net-(C12-Pad1)") (class "Default")
      (node (ref "C12") (pin "1") (pinfunction "1_1") (pintype "passive"))
      (node (ref "R17") (pin "1") (pinfunction "1_1") (pintype "passive"))
      (node (ref "R25") (pin "2") (pinfunction "2_2") (pintype "passive"))
    )
    (net (code "37") (name "Net-(C13-Pad1)") (class "Default")
      (node (ref "C13") (pin "1") (pinfunction "1_1") (pintype "passive"))
      (node (ref "IC301") (pin "IN") (pinfunction "IN_IN") (pintype "input"))
      (node (ref "R302") (pin "2") (pinfunction "2_2") (pintype "passive"))
    )
    (net (code "38") (name "Net-(C14-Pad1)") (class "Default")
      (node (ref "C14") (pin "1") (pinfunction "1_1") (pintype "passive"))
      (node (ref "IC302") (pin "IN") (pinfunction "IN_IN") (pintype "input"))
      (node (ref "R303") (pin "2") (pinfunction "2_2") (pintype "passive"))
    )
    (net (code "39") (name "Net-(C23-Pad1)") (class "Default")
      (node (ref "C23") (pin "1") (pinfunction "1_1") (pintype "passive"))
      (node (ref "C301") (pin "+") (pinfunction "+_+") (pintype "passive"))
      (node (ref "D1") (pin "C") (pinfunction "C_C") (pintype "passive"))
      (node (ref "L4") (pin "1") (pinfunction "1_1") (pintype "passive"))
      (node (ref "R301") (pin "2") (pinfunction "2_2") (pintype "passive"))
    )
    (net (code "40") (name "Net-(C102-Pad1)") (class "Default")
      (node (ref "C102") (pin "1") (pinfunction "1_1") (pintype "passive"))
      (node (ref "R107") (pin "2") (pinfunction "2_2") (pintype "passive"))
      (node (ref "R108") (pin "1") (pinfunction "1_1") (pintype "passive"))
    )
    (net (code "41") (name "Net-(C104-Pad1)") (class "Default")
      (node (ref "C104") (pin "1") (pinfunction "1_1") (pintype "passive"))
      (node (ref "R109") (pin "2") (pinfunction "2_2") (pintype "passive"))
      (node (ref "R110") (pin "1") (pinfunction "1_1") (pintype "passive"))
    )
    (net (code "42") (name "Net-(C106-Pad1)") (class "Default")
      (node (ref "C106") (pin "1") (pinfunction "1_1") (pintype "passive"))
      (node (ref "R111") (pin "2") (pinfunction "2_2") (pintype "passive"))
    )
    (net (code "43") (name "Net-(C107-Pad1)") (class "Default")
      (node (ref "C107") (pin "1") (pinfunction "1_1") (pintype "passive"))
      (node (ref "R112") (pin "2") (pinfunction "2_2") (pintype "passive"))
    )
    (net (code "44") (name "Net-(C109-Pad1)") (class "Default")
      (node (ref "C109") (pin "1") (pinfunction "1_1") (pintype "passive"))
      (node (ref "R115") (pin "2") (pinfunction "2_2") (pintype "passive"))
    )
    (net (code "45") (name "Net-(C110-Pad1)") (class "Default")
      (node (ref "C110") (pin "1") (pinfunction "1_1") (pintype "passive"))
      (node (ref "R116") (pin "2") (pinfunction "2_2") (pintype "passive"))
    )
    (net (code "46") (name "Net-(C111-Pad1)") (class "Default")
      (node (ref "C111") (pin "1") (pinfunction "1_1") (pintype "passive"))
      (node (ref "R117") (pin "2") (pinfunction "2_2") (pintype "passive"))
      (node (ref "R118") (pin "2") (pinfunction "2_2") (pintype "passive"))
    )
    (net (code "47") (name "Net-(C112-Pad1)") (class "Default")
      (node (ref "C112") (pin "1") (pinfunction "1_1") (pintype "passive"))
      (node (ref "R119") (pin "2") (pinfunction "2_2") (pintype "passive"))
      (node (ref "R120") (pin "2") (pinfunction "2_2") (pintype "passive"))
    )
    (net (code "48") (name "Net-(C207-Pad1)") (class "Default")
      (node (ref "C207") (pin "1") (pinfunction "1_1") (pintype "passive"))
      (node (ref "R214") (pin "1") (pinfunction "1_1") (pintype "passive"))
    )
    (net (code "49") (name "Net-(C209-Pad1)") (class "Default")
      (node (ref "C209") (pin "1") (pinfunction "1_1") (pintype "passive"))
      (node (ref "R216") (pin "2") (pinfunction "2_2") (pintype "passive"))
    )
    (net (code "50") (name "Net-(C303-Pad1)") (class "Default")
      (node (ref "C303") (pin "1") (pinfunction "1_1") (pintype "passive"))
      (node (ref "L4") (pin "2") (pinfunction "2_2") (pintype "passive"))
      (node (ref "L5") (pin "1") (pinfunction "1_1") (pintype "passive"))
      (node (ref "R40") (pin "1") (pinfunction "1_1") (pintype "passive"))
    )
    (net (code "51") (name "Net-(D1-PadA)") (class "Default")
      (node (ref "D1") (pin "A") (pinfunction "A_A") (pintype "passive"))
      (node (ref "R302") (pin "1") (pinfunction "1_1") (pintype "passive"))
      (node (ref "R303") (pin "1") (pinfunction "1_1") (pintype "passive"))
    )
    (net (code "52") (name "Net-(D301-PadC)") (class "Default")
      (node (ref "D301") (pin "C") (pinfunction "C_C") (pintype "passive"))
      (node (ref "J1") (pin "2") (pinfunction "2_2") (pintype "passive"))
      (node (ref "R301") (pin "1") (pinfunction "1_1") (pintype "passive"))
    )
    (net (code "53") (name "Net-(IC201A-I)") (class "Default")
      (node (ref "IC201") (pin "2") (pinfunction "I_2") (pintype "input"))
      (node (ref "J202") (pin "C") (pinfunction "1_C") (pintype "passive"))
      (node (ref "R204") (pin "1") (pinfunction "1_1") (pintype "passive"))
    )
    (net (code "54") (name "Net-(IC201A-O)") (class "Default")
      (node (ref "IC201") (pin "4") (pinfunction "O_4") (pintype "output"))
      (node (ref "Q201") (pin "1") (pinfunction "G_1") (pintype "passive"))
      (node (ref "R41") (pin "2") (pinfunction "2_2") (pintype "passive"))
    )
    (net (code "55") (name "Net-(IC202A-+IN)") (class "Default")
      (node (ref "C208") (pin "1") (pinfunction "1_1") (pintype "passive"))
      (node (ref "IC202") (pin "3") (pinfunction "+IN_3") (pintype "input"))
      (node (ref "R209") (pin "2") (pinfunction "2_2") (pintype "passive"))
      (node (ref "R211") (pin "1") (pinfunction "1_1") (pintype "passive"))
    )
    (net (code "56") (name "Net-(IC202A--IN)") (class "Default")
      (node (ref "C209") (pin "2") (pinfunction "2_2") (pintype "passive"))
      (node (ref "IC202") (pin "2") (pinfunction "-IN_2") (pintype "input"))
      (node (ref "R212") (pin "2") (pinfunction "2_2") (pintype "passive"))
      (node (ref "R214") (pin "2") (pinfunction "2_2") (pintype "passive"))
      (node (ref "R219") (pin "1") (pinfunction "1_1") (pintype "passive"))
    )
    (net (code "57") (name "Net-(IC202A-OUT)") (class "Default")
      (node (ref "IC202") (pin "1") (pinfunction "OUT_1") (pintype "output"))
      (node (ref "R216") (pin "1") (pinfunction "1_1") (pintype "passive"))
      (node (ref "R217") (pin "1") (pinfunction "1_1") (pintype "passive"))
    )
    (net (code "58") (name "Net-(IC202B-+IN)") (class "Default")
      (node (ref "IC202") (pin "5") (pinfunction "+IN_5") (pintype "input"))
      (node (ref "Q201") (pin "3") (pinfunction "D_3") (pintype "passive"))
      (node (ref "R207") (pin "2") (pinfunction "2_2") (pintype "passive"))
    )
    (net (code "59") (name "Net-(IC202B--IN)") (class "Default")
      (node (ref "IC202") (pin "6") (pinfunction "-IN_6") (pintype "input"))
      (node (ref "IC202") (pin "7") (pinfunction "OUT_7") (pintype "output"))
      (node (ref "R209") (pin "1") (pinfunction "1_1") (pintype "passive"))
      (node (ref "TP12") (pin "TP") (pinfunction "1_TP") (pintype "passive"))
    )
    (net (code "60") (name "Net-(IC202C-+IN)") (class "Default")
      (node (ref "IC202") (pin "10") (pinfunction "+IN_10") (pintype "input"))
      (node (ref "R203") (pin "2") (pinfunction "2_2") (pintype "passive"))
      (node (ref "R206") (pin "1") (pinfunction "1_1") (pintype "passive"))
    )
    (net (code "61") (name "Net-(IC202C--IN)") (class "Default")
      (node (ref "IC202") (pin "9") (pinfunction "-IN_9") (pintype "input"))
      (node (ref "JP202") (pin "1") (pinfunction "1_1") (pintype "passive"))
      (node (ref "R202") (pin "2") (pinfunction "2_2") (pintype "passive"))
      (node (ref "R205") (pin "1") (pinfunction "1_1") (pintype "passive"))
    )
    (net (code "62") (name "Net-(IC202C-OUT)") (class "Default")
      (node (ref "IC202") (pin "8") (pinfunction "OUT_8") (pintype "output"))
      (node (ref "JP202") (pin "2") (pinfunction "2_2") (pintype "passive"))
      (node (ref "R205") (pin "2") (pinfunction "2_2") (pintype "passive"))
      (node (ref "R207") (pin "1") (pinfunction "1_1") (pintype "passive"))
    )
    (net (code "63") (name "Net-(IC202D-+IN)") (class "Default")
      (node (ref "C201") (pin "1") (pinfunction "1_1") (pintype "passive"))
      (node (ref "IC202") (pin "12") (pinfunction "+IN_12") (pintype "input"))
      (node (ref "R201") (pin "2") (pinfunction "S_2") (pintype "passive"))
    )
    (net (code "64") (name "Net-(IC202D--IN)") (class "Default")
      (node (ref "IC202") (pin "13") (pinfunction "-IN_13") (pintype "input"))
      (node (ref "IC202") (pin "14") (pinfunction "OUT_14") (pintype "output"))
      (node (ref "R206") (pin "2") (pinfunction "2_2") (pintype "passive"))
      (node (ref "TP13") (pin "TP") (pinfunction "1_TP") (pintype "passive"))
    )
    (net (code "65") (name "Net-(J2-Pad3)") (class "Default")
      (node (ref "J2") (pin "3") (pinfunction "3_3") (pintype "passive"))
      (node (ref "R29") (pin "2") (pinfunction "2_2") (pintype "passive"))
    )
    (net (code "66") (name "Net-(J101-1)") (class "Default")
      (node (ref "C101") (pin "1") (pinfunction "1_1") (pintype "passive"))
      (node (ref "J101") (pin "C") (pinfunction "1_C") (pintype "passive"))
    )
    (net (code "67") (name "Net-(J102-1)") (class "Default")
      (node (ref "C117") (pin "2") (pinfunction "2_2") (pintype "passive"))
      (node (ref "J102") (pin "C") (pinfunction "1_C") (pintype "passive"))
    )
    (net (code "68") (name "Net-(J201-1)") (class "Default")
      (node (ref "J201") (pin "C") (pinfunction "1_C") (pintype "passive"))
      (node (ref "JP201") (pin "2") (pinfunction "2_2") (pintype "passive"))
      (node (ref "R202") (pin "1") (pinfunction "1_1") (pintype "passive"))
    )
    (net (code "69") (name "Net-(J201-GND1-PadG1)") (class "Default")
      (node (ref "J201") (pin "G1") (pinfunction "GND1_G1") (pintype "power_in"))
      (node (ref "J201") (pin "G2") (pinfunction "GND1_G2") (pintype "power_in"))
      (node (ref "J201") (pin "G3") (pinfunction "GND1_G3") (pintype "power_in"))
      (node (ref "J201") (pin "G4") (pinfunction "GND1_G4") (pintype "power_in"))
      (node (ref "JP201") (pin "1") (pinfunction "1_1") (pintype "passive"))
      (node (ref "R203") (pin "1") (pinfunction "1_1") (pintype "passive"))
    )
    (net (code "70") (name "Net-(LED1-C)") (class "Default")
      (node (ref "LED1") (pin "K") (pinfunction "C_K") (pintype "passive"))
      (node (ref "R28") (pin "1") (pinfunction "1_1") (pintype "passive"))
    )
    (net (code "71") (name "Net-(LED2-C)") (class "Default")
      (node (ref "LED2") (pin "K") (pinfunction "C_K") (pintype "passive"))
      (node (ref "R27") (pin "1") (pinfunction "1_1") (pintype "passive"))
    )
    (net (code "72") (name "Net-(LED3-C)") (class "Default")
      (node (ref "LED3") (pin "K") (pinfunction "C_K") (pintype "passive"))
      (node (ref "R41") (pin "1") (pinfunction "1_1") (pintype "passive"))
    )
    (net (code "73") (name "Net-(R217-Pad2)") (class "Default")
      (node (ref "R217") (pin "2") (pinfunction "2_2") (pintype "passive"))
      (node (ref "R218") (pin "1") (pinfunction "1_1") (pintype "passive"))
      (node (ref "T201") (pin "B") (pinfunction "B_B") (pintype "passive"))
      (node (ref "T202") (pin "B") (pinfunction "B_B") (pintype "passive"))
    )
    (net (code "74") (name "Net-(T1-F1)") (class "Default")
      (node (ref "R31") (pin "1") (pinfunction "1_1") (pintype "passive"))
      (node (ref "T1") (pin "12") (pinfunction "F1_12") (pintype "passive"))
      (node (ref "T1") (pin "2") (pinfunction "S2_2") (pintype "passive"))
    )
    (net (code "75") (name "Net-(T1-F4)") (class "Default")
      (node (ref "T1") (pin "3") (pinfunction "S3_3") (pintype "passive"))
      (node (ref "T1") (pin "9") (pinfunction "F4_9") (pintype "passive"))
    )
    (net (code "76") (name "Net-(T1-F5)") (class "Default")
      (node (ref "T1") (pin "4") (pinfunction "S4_4") (pintype "passive"))
      (node (ref "T1") (pin "8") (pinfunction "F5_8") (pintype "passive"))
    )
    (net (code "77") (name "Net-(T1-F6)") (class "Default")
      (node (ref "T1") (pin "5") (pinfunction "S5_5") (pintype "passive"))
      (node (ref "T1") (pin "7") (pinfunction "F6_7") (pintype "passive"))
    )
    (net (code "78") (name "Net-(T1-S6)") (class "Default")
      (node (ref "C101") (pin "2") (pinfunction "2_2") (pintype "passive"))
      (node (ref "T1") (pin "6") (pinfunction "S6_6") (pintype "passive"))
    )
    (net (code "79") (name "Net-(T2-F1)") (class "Default")
      (node (ref "T2") (pin "12") (pinfunction "F1_12") (pintype "passive"))
      (node (ref "T2") (pin "2") (pinfunction "S2_2") (pintype "passive"))
    )
    (net (code "80") (name "Net-(T2-F2)") (class "Default")
      (node (ref "T2") (pin "11") (pinfunction "F2_11") (pintype "passive"))
      (node (ref "T2") (pin "3") (pinfunction "S3_3") (pintype "passive"))
    )
    (net (code "81") (name "Net-(T2-F3)") (class "Default")
      (node (ref "T2") (pin "10") (pinfunction "F3_10") (pintype "passive"))
      (node (ref "T2") (pin "4") (pinfunction "S4_4") (pintype "passive"))
    )
    (net (code "82") (name "Net-(T2-F6)") (class "Default")
      (node (ref "R30") (pin "2") (pinfunction "2_2") (pintype "passive"))
      (node (ref "T2") (pin "5") (pinfunction "S5_5") (pintype "passive"))
      (node (ref "T2") (pin "7") (pinfunction "F6_7") (pintype "passive"))
    )
    (net (code "83") (name "Net-(T2-S1)") (class "Default")
      (node (ref "C117") (pin "1") (pinfunction "1_1") (pintype "passive"))
      (node (ref "T2") (pin "1") (pinfunction "S1_1") (pintype "passive"))
    )
    (net (code "84") (name "Net-(X1A-KL)") (class "Default")
      (node (ref "J1") (pin "1") (pinfunction "1_1") (pintype "passive"))
      (node (ref "X1") (pin "1") (pinfunction "KL_1") (pintype "passive"))
    )
    (net (code "85") (name "VB") (class "Default")
      (node (ref "C17") (pin "1") (pinfunction "1_1") (pintype "passive"))
      (node (ref "C18") (pin "1") (pinfunction "1_1") (pintype "passive"))
      (node (ref "C19") (pin "1") (pinfunction "1_1") (pintype "passive"))
      (node (ref "C20") (pin "1") (pinfunction "1_1") (pintype "passive"))
      (node (ref "C21") (pin "1") (pinfunction "1_1") (pintype "passive"))
      (node (ref "C304") (pin "1") (pinfunction "1_1") (pintype "passive"))
      (node (ref "L5") (pin "2") (pinfunction "2_2") (pintype "passive"))
      (node (ref "L6") (pin "2") (pinfunction "2_2") (pintype "passive"))
      (node (ref "L7") (pin "2") (pinfunction "2_2") (pintype "passive"))
      (node (ref "R30") (pin "1") (pinfunction "1_1") (pintype "passive"))
      (node (ref "R40") (pin "2") (pinfunction "2_2") (pintype "passive"))
    )
    (net (code "86") (name "unconnected-(J2-Pad4)") (class "Default")
      (node (ref "J2") (pin "4") (pinfunction "4_4") (pintype "passive"))
    )
  )
)
